# homeboard18.net
KiCad netlist of a schematic drawn in EAGLE
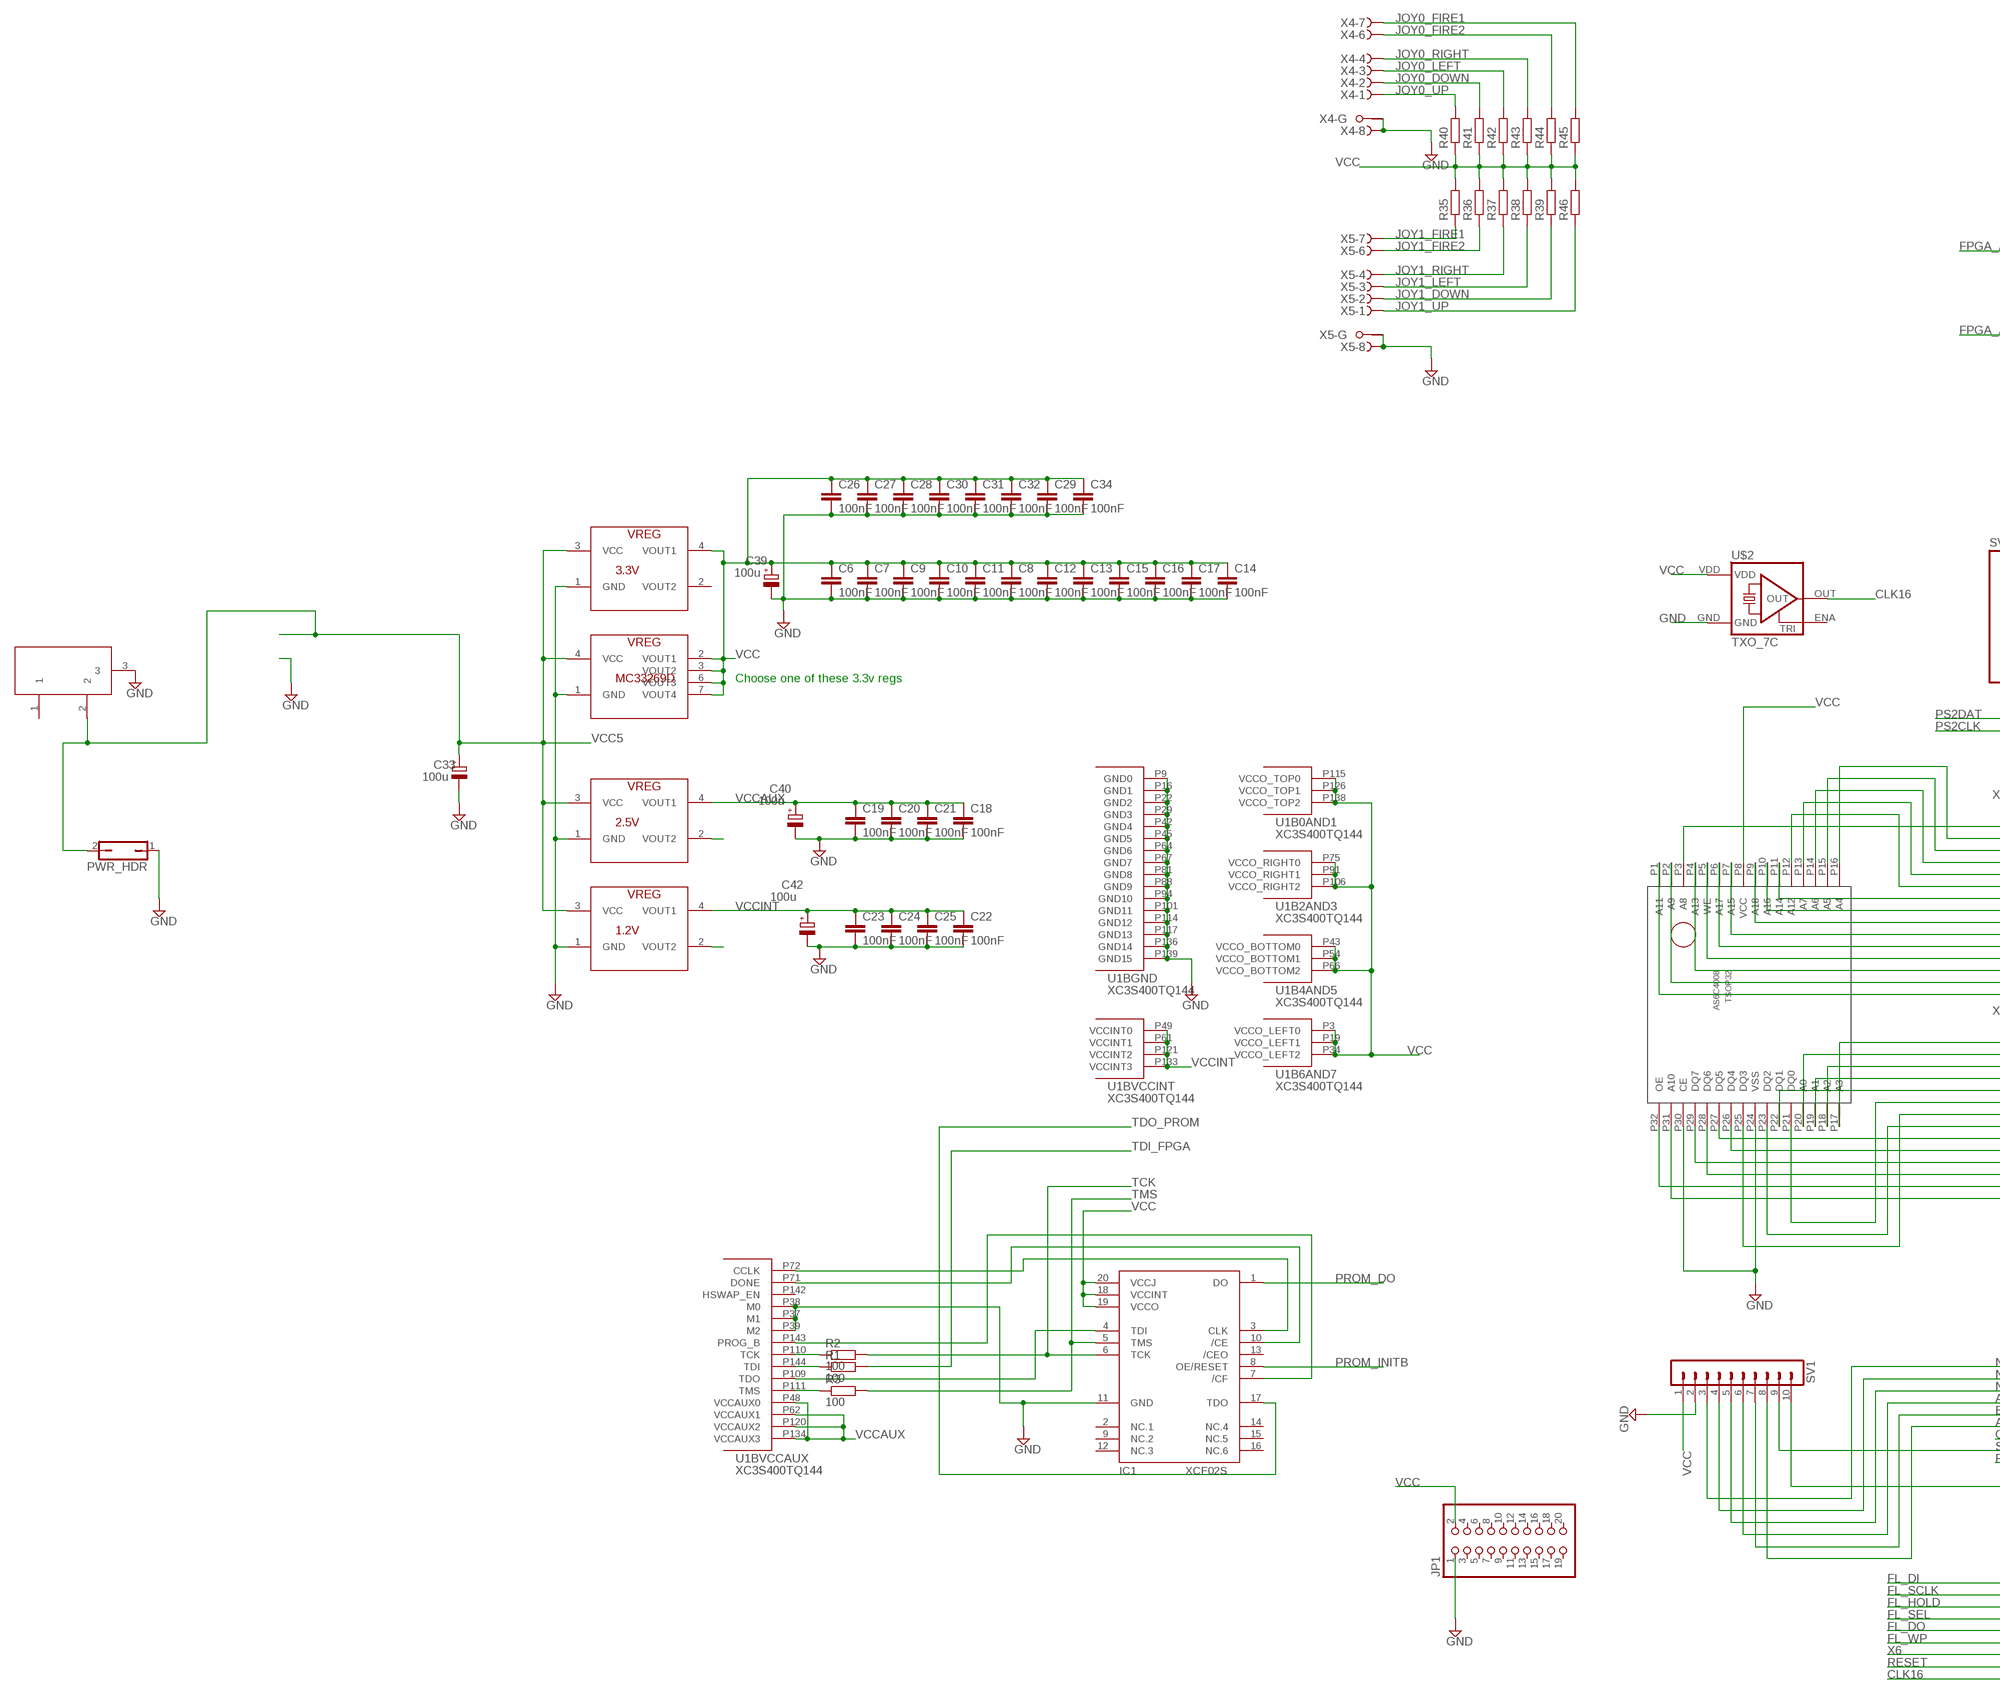
[diagram p0: schematic, sheet 1, part 1 of 3]
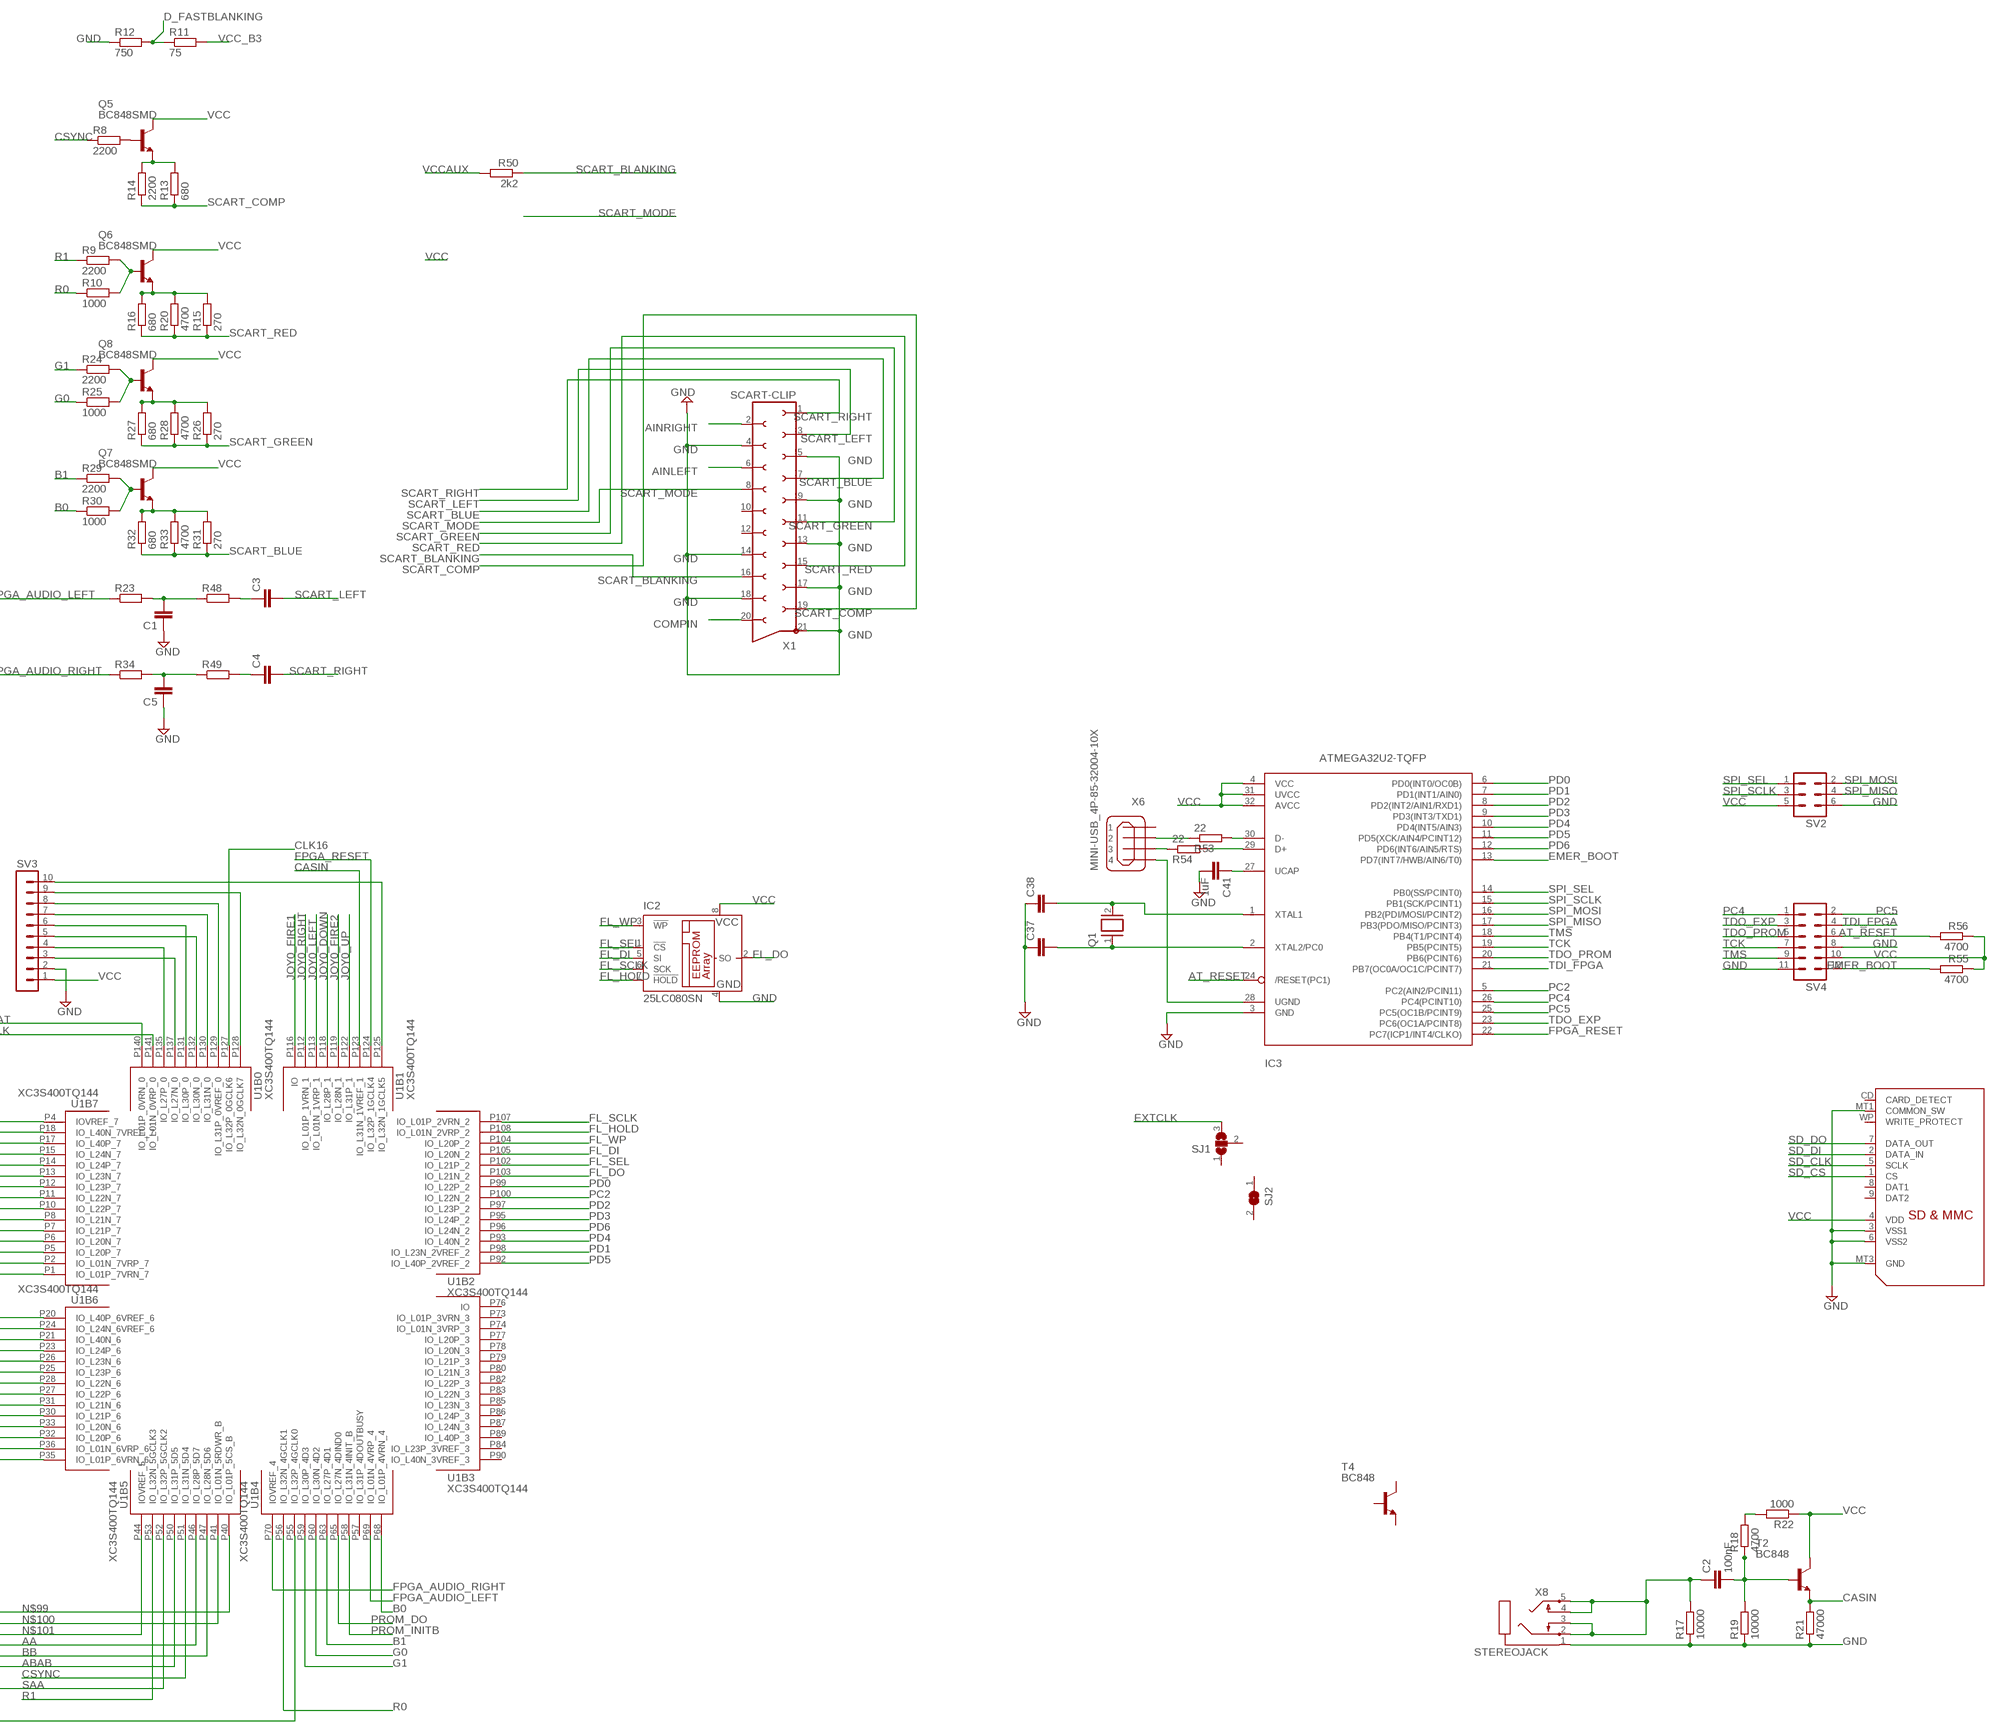
[diagram p1: schematic, sheet 1, part 2 of 3]
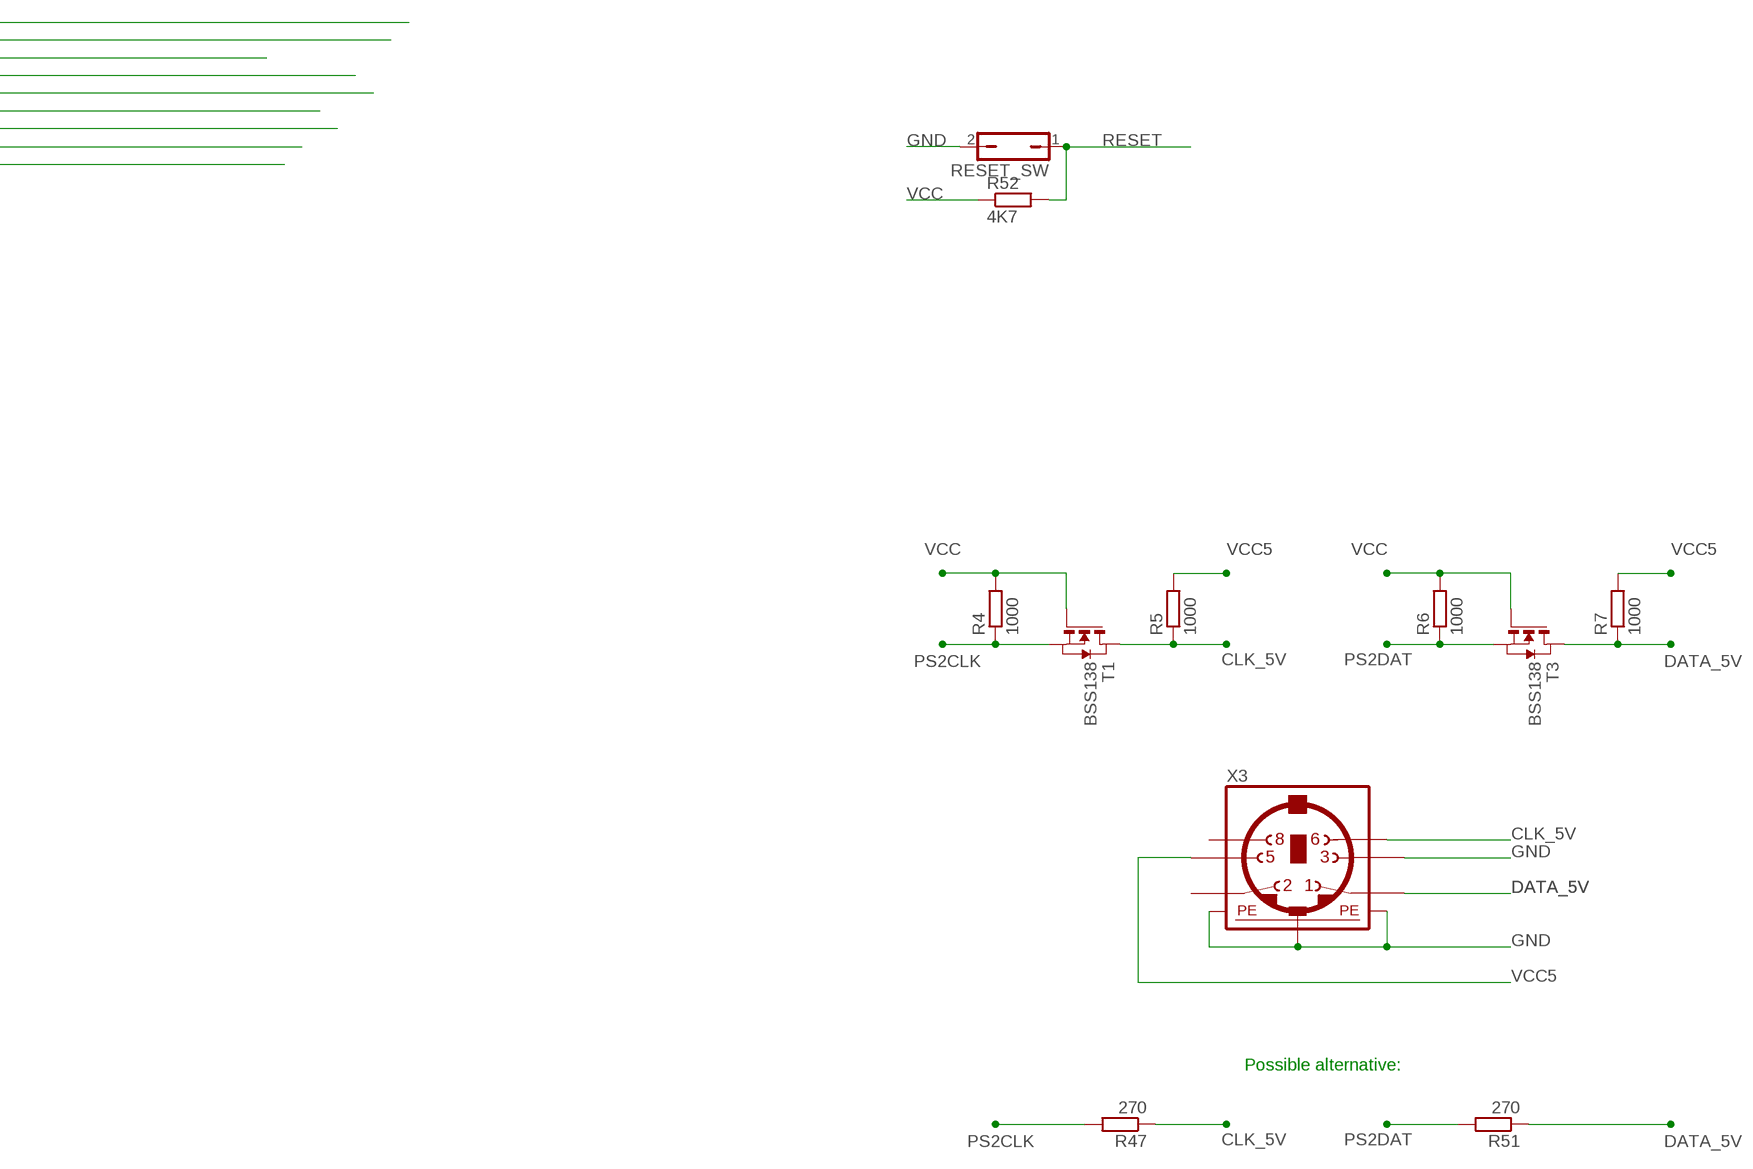
[diagram p2: schematic, sheet 1, part 3 of 3]

(export (version "E")
  (design (tool "Eeschema 10.0.6"))
  (components
    (comp (ref "C1")
      (value "C-EUC0603")
      (footprint "eagle-import:C0603")
      (libsource (lib "eagle-import") (part "resistor_C-EUC0603"))
    )
    (comp (ref "C2")
      (value "100nF")
      (footprint "eagle-import:C0603")
      (libsource (lib "eagle-import") (part "resistor_C-EUC0603"))
    )
    (comp (ref "C3")
      (value "C-EUC0603")
      (footprint "eagle-import:C0603")
      (libsource (lib "eagle-import") (part "resistor_C-EUC0603"))
    )
    (comp (ref "C4")
      (value "C-EUC0603")
      (footprint "eagle-import:C0603")
      (libsource (lib "eagle-import") (part "resistor_C-EUC0603"))
    )
    (comp (ref "C5")
      (value "C-EUC0603")
      (footprint "eagle-import:C0603")
      (libsource (lib "eagle-import") (part "resistor_C-EUC0603"))
    )
    (comp (ref "C6")
      (value "100nF")
      (footprint "eagle-import:C0603")
      (libsource (lib "eagle-import") (part "C-EUC0603"))
    )
    (comp (ref "C7")
      (value "100nF")
      (footprint "eagle-import:C0603")
      (libsource (lib "eagle-import") (part "C-EUC0603"))
    )
    (comp (ref "C8")
      (value "100nF")
      (footprint "eagle-import:C0603")
      (libsource (lib "eagle-import") (part "C-EUC0603"))
    )
    (comp (ref "C9")
      (value "100nF")
      (footprint "eagle-import:C0603")
      (libsource (lib "eagle-import") (part "C-EUC0603"))
    )
    (comp (ref "C10")
      (value "100nF")
      (footprint "eagle-import:C0603")
      (libsource (lib "eagle-import") (part "C-EUC0603"))
    )
    (comp (ref "C11")
      (value "100nF")
      (footprint "eagle-import:C0603")
      (libsource (lib "eagle-import") (part "C-EUC0603"))
    )
    (comp (ref "C12")
      (value "100nF")
      (footprint "eagle-import:C0603")
      (libsource (lib "eagle-import") (part "C-EUC0603"))
    )
    (comp (ref "C13")
      (value "100nF")
      (footprint "eagle-import:C0603")
      (libsource (lib "eagle-import") (part "C-EUC0603"))
    )
    (comp (ref "C14")
      (value "100nF")
      (footprint "eagle-import:C0603")
      (libsource (lib "eagle-import") (part "C-EUC0603"))
    )
    (comp (ref "C15")
      (value "100nF")
      (footprint "eagle-import:C0603")
      (libsource (lib "eagle-import") (part "C-EUC0603"))
    )
    (comp (ref "C16")
      (value "100nF")
      (footprint "eagle-import:C0603")
      (libsource (lib "eagle-import") (part "C-EUC0603"))
    )
    (comp (ref "C17")
      (value "100nF")
      (footprint "eagle-import:C0603")
      (libsource (lib "eagle-import") (part "C-EUC0603"))
    )
    (comp (ref "C18")
      (value "100nF")
      (footprint "eagle-import:C0603")
      (libsource (lib "eagle-import") (part "C-EUC0603"))
    )
    (comp (ref "C19")
      (value "100nF")
      (footprint "eagle-import:C0603")
      (libsource (lib "eagle-import") (part "C-EUC0603"))
    )
    (comp (ref "C20")
      (value "100nF")
      (footprint "eagle-import:C0603")
      (libsource (lib "eagle-import") (part "C-EUC0603"))
    )
    (comp (ref "C21")
      (value "100nF")
      (footprint "eagle-import:C0603")
      (libsource (lib "eagle-import") (part "C-EUC0603"))
    )
    (comp (ref "C22")
      (value "100nF")
      (footprint "eagle-import:C0603")
      (libsource (lib "eagle-import") (part "C-EUC0603"))
    )
    (comp (ref "C23")
      (value "100nF")
      (footprint "eagle-import:C0603")
      (libsource (lib "eagle-import") (part "C-EUC0603"))
    )
    (comp (ref "C24")
      (value "100nF")
      (footprint "eagle-import:C0603")
      (libsource (lib "eagle-import") (part "C-EUC0603"))
    )
    (comp (ref "C25")
      (value "100nF")
      (footprint "eagle-import:C0603")
      (libsource (lib "eagle-import") (part "C-EUC0603"))
    )
    (comp (ref "C26")
      (value "100nF")
      (footprint "eagle-import:C0603")
      (libsource (lib "eagle-import") (part "C-EUC0603"))
    )
    (comp (ref "C27")
      (value "100nF")
      (footprint "eagle-import:C0603")
      (libsource (lib "eagle-import") (part "C-EUC0603"))
    )
    (comp (ref "C28")
      (value "100nF")
      (footprint "eagle-import:C0603")
      (libsource (lib "eagle-import") (part "C-EUC0603"))
    )
    (comp (ref "C29")
      (value "100nF")
      (footprint "eagle-import:C0603")
      (libsource (lib "eagle-import") (part "C-EUC0603"))
    )
    (comp (ref "C30")
      (value "100nF")
      (footprint "eagle-import:C0603")
      (libsource (lib "eagle-import") (part "C-EUC0603"))
    )
    (comp (ref "C31")
      (value "100nF")
      (footprint "eagle-import:C0603")
      (libsource (lib "eagle-import") (part "C-EUC0603"))
    )
    (comp (ref "C32")
      (value "100nF")
      (footprint "eagle-import:C0603")
      (libsource (lib "eagle-import") (part "C-EUC0603"))
    )
    (comp (ref "C33")
      (value "100u")
      (footprint "eagle-import:PANASONIC_D")
      (libsource (lib "eagle-import") (part "CPOL-EUD"))
    )
    (comp (ref "C34")
      (value "100nF")
      (footprint "eagle-import:C0603")
      (libsource (lib "eagle-import") (part "C-EUC0603"))
    )
    (comp (ref "C37")
      (value "C-EUC0805")
      (footprint "eagle-import:C0805")
      (libsource (lib "eagle-import") (part "C-EUC0805"))
    )
    (comp (ref "C38")
      (value "C-EUC0805")
      (footprint "eagle-import:C0805")
      (libsource (lib "eagle-import") (part "C-EUC0805"))
    )
    (comp (ref "C39")
      (value "100u")
      (footprint "eagle-import:PANASONIC_D")
      (libsource (lib "eagle-import") (part "CPOL-EUD"))
    )
    (comp (ref "C40")
      (value "100u")
      (footprint "eagle-import:PANASONIC_D")
      (libsource (lib "eagle-import") (part "CPOL-EUD"))
    )
    (comp (ref "C41")
      (value "1uF")
      (footprint "eagle-import:C0805")
      (libsource (lib "eagle-import") (part "C-EUC0805"))
    )
    (comp (ref "C42")
      (value "100u")
      (footprint "eagle-import:PANASONIC_D")
      (libsource (lib "eagle-import") (part "CPOL-EUD"))
    )
    (comp (ref "IC1")
      (value "XCF02S")
      (footprint "eagle-import:VO20")
      (libsource (lib "eagle-import") (part "XCF02S"))
    )
    (comp (ref "IC2")
      (value "25LC080SN")
      (footprint "eagle-import:SO-08")
      (fields (field (name "MF") "MICROCHIP") (field (name "MPN") "25LC080/SN"))
      (libsource (lib "eagle-import") (part "25SNLC080"))
    )
    (comp (ref "IC3")
      (value "ATMEGA32U2-TQFP")
      (footprint "eagle-import:TQFP32-08")
      (libsource (lib "eagle-import") (part "ATMEGA32U2-TQFP"))
    )
    (comp (ref "JP1")
      (value "PINHD-2X10")
      (footprint "eagle-import:2X10")
      (libsource (lib "eagle-import") (part "PINHD-2X10"))
    )
    (comp (ref "PWR_HDR")
      (value "JP1Q")
      (footprint "eagle-import:JP1")
      (libsource (lib "eagle-import") (part "JP1Q"))
    )
    (comp (ref "Q1")
      (value "XTAL/S")
      (footprint "eagle-import:QS")
      (libsource (lib "eagle-import") (part "XTAL/S"))
    )
    (comp (ref "Q5")
      (value "BC848SMD")
      (footprint "eagle-import:SOT23")
      (libsource (lib "eagle-import") (part "BC848SMD"))
    )
    (comp (ref "Q6")
      (value "BC848SMD")
      (footprint "eagle-import:SOT23")
      (libsource (lib "eagle-import") (part "BC848SMD"))
    )
    (comp (ref "Q7")
      (value "BC848SMD")
      (footprint "eagle-import:SOT23")
      (libsource (lib "eagle-import") (part "BC848SMD"))
    )
    (comp (ref "Q8")
      (value "BC848SMD")
      (footprint "eagle-import:SOT23")
      (libsource (lib "eagle-import") (part "BC848SMD"))
    )
    (comp (ref "R1")
      (value "100")
      (footprint "eagle-import:R0805")
      (libsource (lib "eagle-import") (part "R-EU_R0805"))
    )
    (comp (ref "R2")
      (value "100")
      (footprint "eagle-import:R0805")
      (libsource (lib "eagle-import") (part "R-EU_R0805"))
    )
    (comp (ref "R3")
      (value "100")
      (footprint "eagle-import:R0805")
      (libsource (lib "eagle-import") (part "R-EU_R0805"))
    )
    (comp (ref "R4")
      (value "1000")
      (footprint "eagle-import:R0805")
      (libsource (lib "eagle-import") (part "R-EU_R0805"))
    )
    (comp (ref "R5")
      (value "1000")
      (footprint "eagle-import:R0805")
      (libsource (lib "eagle-import") (part "R-EU_R0805"))
    )
    (comp (ref "R6")
      (value "1000")
      (footprint "eagle-import:R0805")
      (libsource (lib "eagle-import") (part "R-EU_R0805"))
    )
    (comp (ref "R7")
      (value "1000")
      (footprint "eagle-import:R0805")
      (libsource (lib "eagle-import") (part "R-EU_R0805"))
    )
    (comp (ref "R8")
      (value "2200")
      (footprint "eagle-import:R0805")
      (libsource (lib "eagle-import") (part "R-EU_R0805"))
    )
    (comp (ref "R9")
      (value "2200")
      (footprint "eagle-import:R0805")
      (libsource (lib "eagle-import") (part "R-EU_R0805"))
    )
    (comp (ref "R10")
      (value "1000")
      (footprint "eagle-import:R0805")
      (libsource (lib "eagle-import") (part "R-EU_R0805"))
    )
    (comp (ref "R11")
      (value "75")
      (footprint "eagle-import:R0805")
      (libsource (lib "eagle-import") (part "R-EU_R0805"))
    )
    (comp (ref "R12")
      (value "750")
      (footprint "eagle-import:R0805")
      (libsource (lib "eagle-import") (part "R-EU_R0805"))
    )
    (comp (ref "R13")
      (value "680")
      (footprint "eagle-import:R0805")
      (libsource (lib "eagle-import") (part "R-EU_R0805"))
    )
    (comp (ref "R14")
      (value "2200")
      (footprint "eagle-import:R0805")
      (libsource (lib "eagle-import") (part "R-EU_R0805"))
    )
    (comp (ref "R15")
      (value "270")
      (footprint "eagle-import:R0805")
      (libsource (lib "eagle-import") (part "R-EU_R0805"))
    )
    (comp (ref "R16")
      (value "680")
      (footprint "eagle-import:R0805")
      (libsource (lib "eagle-import") (part "R-EU_R0805"))
    )
    (comp (ref "R17")
      (value "10000")
      (footprint "eagle-import:R0805")
      (libsource (lib "eagle-import") (part "R-EU_R0805"))
    )
    (comp (ref "R18")
      (value "4700")
      (footprint "eagle-import:R0805")
      (libsource (lib "eagle-import") (part "R-EU_R0805"))
    )
    (comp (ref "R19")
      (value "10000")
      (footprint "eagle-import:R0805")
      (libsource (lib "eagle-import") (part "R-EU_R0805"))
    )
    (comp (ref "R20")
      (value "4700")
      (footprint "eagle-import:R0805")
      (libsource (lib "eagle-import") (part "R-EU_R0805"))
    )
    (comp (ref "R21")
      (value "47000")
      (footprint "eagle-import:R0805")
      (libsource (lib "eagle-import") (part "R-EU_R0805"))
    )
    (comp (ref "R22")
      (value "1000")
      (footprint "eagle-import:R0805")
      (libsource (lib "eagle-import") (part "R-EU_R0805"))
    )
    (comp (ref "R23")
      (value "R-EU_M0805")
      (footprint "eagle-import:M0805")
      (libsource (lib "eagle-import") (part "resistor_R-EU_M0805"))
    )
    (comp (ref "R24")
      (value "2200")
      (footprint "eagle-import:R0805")
      (libsource (lib "eagle-import") (part "R-EU_R0805"))
    )
    (comp (ref "R25")
      (value "1000")
      (footprint "eagle-import:R0805")
      (libsource (lib "eagle-import") (part "R-EU_R0805"))
    )
    (comp (ref "R26")
      (value "270")
      (footprint "eagle-import:R0805")
      (libsource (lib "eagle-import") (part "R-EU_R0805"))
    )
    (comp (ref "R27")
      (value "680")
      (footprint "eagle-import:R0805")
      (libsource (lib "eagle-import") (part "R-EU_R0805"))
    )
    (comp (ref "R28")
      (value "4700")
      (footprint "eagle-import:R0805")
      (libsource (lib "eagle-import") (part "R-EU_R0805"))
    )
    (comp (ref "R29")
      (value "2200")
      (footprint "eagle-import:R0805")
      (libsource (lib "eagle-import") (part "R-EU_R0805"))
    )
    (comp (ref "R30")
      (value "1000")
      (footprint "eagle-import:R0805")
      (libsource (lib "eagle-import") (part "R-EU_R0805"))
    )
    (comp (ref "R31")
      (value "270")
      (footprint "eagle-import:R0805")
      (libsource (lib "eagle-import") (part "R-EU_R0805"))
    )
    (comp (ref "R32")
      (value "680")
      (footprint "eagle-import:R0805")
      (libsource (lib "eagle-import") (part "R-EU_R0805"))
    )
    (comp (ref "R33")
      (value "4700")
      (footprint "eagle-import:R0805")
      (libsource (lib "eagle-import") (part "R-EU_R0805"))
    )
    (comp (ref "R34")
      (value "R-EU_M0805")
      (footprint "eagle-import:M0805")
      (libsource (lib "eagle-import") (part "resistor_R-EU_M0805"))
    )
    (comp (ref "R35")
      (value "R-EU_M0805")
      (footprint "eagle-import:M0805")
      (libsource (lib "eagle-import") (part "resistor_R-EU_M0805"))
    )
    (comp (ref "R36")
      (value "R-EU_M0805")
      (footprint "eagle-import:M0805")
      (libsource (lib "eagle-import") (part "resistor_R-EU_M0805"))
    )
    (comp (ref "R37")
      (value "R-EU_M0805")
      (footprint "eagle-import:M0805")
      (libsource (lib "eagle-import") (part "resistor_R-EU_M0805"))
    )
    (comp (ref "R38")
      (value "R-EU_M0805")
      (footprint "eagle-import:M0805")
      (libsource (lib "eagle-import") (part "resistor_R-EU_M0805"))
    )
    (comp (ref "R39")
      (value "R-EU_M0805")
      (footprint "eagle-import:M0805")
      (libsource (lib "eagle-import") (part "resistor_R-EU_M0805"))
    )
    (comp (ref "R40")
      (value "R-EU_M0805")
      (footprint "eagle-import:M0805")
      (libsource (lib "eagle-import") (part "resistor_R-EU_M0805"))
    )
    (comp (ref "R41")
      (value "R-EU_M0805")
      (footprint "eagle-import:M0805")
      (libsource (lib "eagle-import") (part "resistor_R-EU_M0805"))
    )
    (comp (ref "R42")
      (value "R-EU_M0805")
      (footprint "eagle-import:M0805")
      (libsource (lib "eagle-import") (part "resistor_R-EU_M0805"))
    )
    (comp (ref "R43")
      (value "R-EU_M0805")
      (footprint "eagle-import:M0805")
      (libsource (lib "eagle-import") (part "resistor_R-EU_M0805"))
    )
    (comp (ref "R44")
      (value "R-EU_M0805")
      (footprint "eagle-import:M0805")
      (libsource (lib "eagle-import") (part "resistor_R-EU_M0805"))
    )
    (comp (ref "R45")
      (value "R-EU_M0805")
      (footprint "eagle-import:M0805")
      (libsource (lib "eagle-import") (part "resistor_R-EU_M0805"))
    )
    (comp (ref "R46")
      (value "R-EU_M0805")
      (footprint "eagle-import:M0805")
      (libsource (lib "eagle-import") (part "resistor_R-EU_M0805"))
    )
    (comp (ref "R47")
      (value "270")
      (footprint "eagle-import:R0805")
      (libsource (lib "eagle-import") (part "R-EU_R0805"))
    )
    (comp (ref "R48")
      (value "R-EU_M0805")
      (footprint "eagle-import:M0805")
      (libsource (lib "eagle-import") (part "resistor_R-EU_M0805"))
    )
    (comp (ref "R49")
      (value "R-EU_M0805")
      (footprint "eagle-import:M0805")
      (libsource (lib "eagle-import") (part "resistor_R-EU_M0805"))
    )
    (comp (ref "R50")
      (value "2k2")
      (footprint "eagle-import:M0805")
      (libsource (lib "eagle-import") (part "resistor_R-EU_M0805"))
    )
    (comp (ref "R51")
      (value "270")
      (footprint "eagle-import:R0805")
      (libsource (lib "eagle-import") (part "R-EU_R0805"))
    )
    (comp (ref "R52")
      (value "4K7")
      (footprint "eagle-import:M0805")
      (libsource (lib "eagle-import") (part "resistor_R-EU_M0805"))
    )
    (comp (ref "R53")
      (value "22")
      (footprint "eagle-import:R0805")
      (libsource (lib "eagle-import") (part "R-EU_R0805"))
    )
    (comp (ref "R54")
      (value "22")
      (footprint "eagle-import:R0805")
      (libsource (lib "eagle-import") (part "R-EU_R0805"))
    )
    (comp (ref "R55")
      (value "4700")
      (footprint "eagle-import:R0805")
      (libsource (lib "eagle-import") (part "R-EU_R0805"))
    )
    (comp (ref "R56")
      (value "4700")
      (footprint "eagle-import:R0805")
      (libsource (lib "eagle-import") (part "R-EU_R0805"))
    )
    (comp (ref "REG1.2")
      (value "1.2V")
      (footprint "eagle-import:SOT223")
      (libsource (lib "eagle-import") (part "NX1117"))
    )
    (comp (ref "REG2.5")
      (value "2.5V")
      (footprint "eagle-import:SOT223")
      (libsource (lib "eagle-import") (part "NX1117"))
    )
    (comp (ref "RESET_SW")
      (value "JP1Q")
      (footprint "eagle-import:JP1")
      (libsource (lib "eagle-import") (part "JP1Q"))
    )
    (comp (ref "SJ1")
      (value "SJ2W")
      (footprint "eagle-import:SJ_2")
      (libsource (lib "eagle-import") (part "SJ2W"))
    )
    (comp (ref "SJ2") (value "SJ") (footprint "eagle-import:SJ") (libsource (lib "eagle-import") (part "SJ")))
    (comp (ref "SV1")
      (value "MA10-1")
      (footprint "eagle-import:MA10-1")
      (fields (field (name "OC_FARNELL") "unknown") (field (name "OC_NEWARK") "unknown"))
      (libsource (lib "eagle-import") (part "MA10-1"))
    )
    (comp (ref "SV2")
      (value "MA03-2")
      (footprint "eagle-import:MA03-2")
      (libsource (lib "eagle-import") (part "MA03-2"))
    )
    (comp (ref "SV3")
      (value "MA10-1")
      (footprint "eagle-import:MA10-1")
      (libsource (lib "eagle-import") (part "MA10-1"))
    )
    (comp (ref "SV4")
      (value "MA06-2")
      (footprint "eagle-import:MA06-2")
      (libsource (lib "eagle-import") (part "MA06-2"))
    )
    (comp (ref "T1")
      (value "BSS138")
      (footprint "eagle-import:SOT-23")
      (libsource (lib "eagle-import") (part "NMOSSOT23"))
    )
    (comp (ref "T2")
      (value "BC848")
      (footprint "eagle-import:SOT23")
      (libsource (lib "eagle-import") (part "BC848"))
    )
    (comp (ref "T3")
      (value "BSS138")
      (footprint "eagle-import:SOT-23")
      (libsource (lib "eagle-import") (part "NMOSSOT23"))
    )
    (comp (ref "T4")
      (value "BC848")
      (footprint "eagle-import:SOT23")
      (libsource (lib "eagle-import") (part "BC848"))
    )
    (comp (ref "U$2")
      (value "TXO_7C")
      (footprint "eagle-import:OSC_7C")
      (libsource (lib "eagle-import") (part "TXO_7C"))
    )
    (comp (ref "U$3")
      (value "SDMMCNOHOLE")
      (footprint "eagle-import:SDCARD-NOHOLE")
      (libsource (lib "eagle-import") (part "SDMMCNOHOLE"))
    )
    (comp (ref "U$4")
      (value "3.3V")
      (footprint "eagle-import:SOT223")
      (libsource (lib "eagle-import") (part "NX1117"))
    )
    (comp (ref "U$5")
      (value "MC33269D")
      (footprint "eagle-import:SO8")
      (libsource (lib "eagle-import") (part "MC33269D"))
    )
    (comp (ref "U$6")
      (value "AS6C4008")
      (footprint "eagle-import:TSOP32")
      (libsource (lib "eagle-import") (part "AS6C4008"))
    )
    (comp (ref "U1")
      (value "XC3S400TQ144")
      (footprint "eagle-import:TQ144")
      (libsource (lib "eagle-import") (part "XC3S400TQ144"))
    )
    (comp (ref "X1")
      (value "SCART-CLIP")
      (footprint "eagle-import:SCART-CLIP")
      (libsource (lib "eagle-import") (part "SCART-CLIP"))
    )
    (comp (ref "X3")
      (value "MINI_DIN_6")
      (footprint "eagle-import:M_DIN6")
      (libsource (lib "eagle-import") (part "MINI_DIN_6"))
    )
    (comp (ref "X4")
      (value "F09HPS")
      (footprint "eagle-import:F09HP")
      (libsource (lib "eagle-import") (part "F09HPS"))
    )
    (comp (ref "X5")
      (value "F09HPS")
      (footprint "eagle-import:F09HP")
      (libsource (lib "eagle-import") (part "F09HPS"))
    )
    (comp (ref "X6")
      (value "MINI-USB_4P-85-32004-10X")
      (footprint "eagle-import:85-32004-10X")
      (libsource (lib "eagle-import") (part "MINI-USB_4P-85-32004-10X"))
    )
    (comp (ref "X7")
      (value "DC21MMX")
      (footprint "eagle-import:DC-21MM")
      (libsource (lib "eagle-import") (part "DC21MMX"))
    )
    (comp (ref "X8")
      (value "STEREOJACK")
      (footprint "eagle-import:20-0137")
      (libsource (lib "eagle-import") (part "STEREOJACK"))
    )
  )
  (nets
    (net (code "1") (name "/1") (class "Default")
      (node (ref "X7") (pin "1") (pinfunction "1_1") (pintype "power_in"))
    )
    (net (code "2") (name "/AA") (class "Default")
      (node (ref "SV1") (pin "6") (pinfunction "6_6") (pintype "passive"))
      (node (ref "U1") (pin "P46") (pinfunction "IO_L28P_5D7_P46") (pintype "bidirectional"))
    )
    (net (code "3") (name "/ABAB") (class "Default")
      (node (ref "SV1") (pin "8") (pinfunction "8_8") (pintype "passive"))
      (node (ref "U1") (pin "P50") (pinfunction "IO_L31P_5D5_P50") (pintype "bidirectional"))
    )
    (net (code "4") (name "/AINLEFT") (class "Default")
      (node (ref "X1") (pin "6") (pinfunction "6_6") (pintype "passive"))
    )
    (net (code "5") (name "/AINRIGHT") (class "Default")
      (node (ref "X1") (pin "2") (pinfunction "2_2") (pintype "passive"))
    )
    (net (code "6") (name "/AT_RESET") (class "Default")
      (node (ref "IC3") (pin "24") (pinfunction "/RESET(PC1)_24") (pintype "bidirectional"))
      (node (ref "R56") (pin "2") (pinfunction "2_2") (pintype "passive"))
      (node (ref "SV4") (pin "6") (pinfunction "6_6") (pintype "passive"))
    )
    (net (code "7") (name "/B0") (class "Default")
      (node (ref "R30") (pin "1") (pinfunction "1_1") (pintype "passive"))
      (node (ref "U1") (pin "P68") (pinfunction "IO_L01P_4VRN_4_P68") (pintype "bidirectional"))
    )
    (net (code "8") (name "/B1") (class "Default")
      (node (ref "R29") (pin "1") (pinfunction "1_1") (pintype "passive"))
      (node (ref "U1") (pin "P63") (pinfunction "IO_L27P_4D1_P63") (pintype "bidirectional"))
    )
    (net (code "9") (name "/BB") (class "Default")
      (node (ref "SV1") (pin "7") (pinfunction "7_7") (pintype "passive"))
      (node (ref "U1") (pin "P47") (pinfunction "IO_L28N_5D6_P47") (pintype "bidirectional"))
    )
    (net (code "10") (name "/CASIN") (class "Default")
      (node (ref "R21") (pin "2") (pinfunction "2_2") (pintype "passive"))
      (node (ref "T2") (pin "2") (pinfunction "E_2") (pintype "passive"))
      (node (ref "U1") (pin "P123") (pinfunction "IO_L31N_1VREF_1_P123") (pintype "bidirectional"))
    )
    (net (code "11") (name "/CLK16") (class "Default")
      (node (ref "U$2") (pin "OUT") (pinfunction "OUT_OUT") (pintype "output"))
      (node (ref "U1") (pin "P127") (pinfunction "IO_L32P_0GCLK6_P127") (pintype "bidirectional"))
    )
    (net (code "12") (name "/CLK_5V") (class "Default")
      (node (ref "R47") (pin "1") (pinfunction "1_1") (pintype "passive"))
      (node (ref "R5") (pin "1") (pinfunction "1_1") (pintype "passive"))
      (node (ref "T1") (pin "1") (pinfunction "D_1") (pintype "passive"))
      (node (ref "X3") (pin "6") (pinfunction "6_6") (pintype "passive"))
    )
    (net (code "13") (name "/COMPIN") (class "Default")
      (node (ref "X1") (pin "20") (pinfunction "20_20") (pintype "passive"))
    )
    (net (code "14") (name "/CSYNC") (class "Default")
      (node (ref "R8") (pin "1") (pinfunction "1_1") (pintype "passive"))
      (node (ref "U1") (pin "P51") (pinfunction "IO_L31N_5D4_P51") (pintype "bidirectional"))
    )
    (net (code "15") (name "/DATA_5V") (class "Default")
      (node (ref "R51") (pin "1") (pinfunction "1_1") (pintype "passive"))
      (node (ref "R7") (pin "1") (pinfunction "1_1") (pintype "passive"))
      (node (ref "T3") (pin "1") (pinfunction "D_1") (pintype "passive"))
      (node (ref "X3") (pin "1") (pinfunction "1_1") (pintype "passive"))
    )
    (net (code "16") (name "/D_FASTBLANKING") (class "Default")
      (node (ref "R11") (pin "1") (pinfunction "1_1") (pintype "passive"))
      (node (ref "R12") (pin "2") (pinfunction "2_2") (pintype "passive"))
    )
    (net (code "17") (name "/EMER_BOOT") (class "Default")
      (node (ref "IC3") (pin "13") (pinfunction "PD7(INT7/HWB/AIN6/T0)_13") (pintype "bidirectional"))
      (node (ref "R55") (pin "2") (pinfunction "2_2") (pintype "passive"))
      (node (ref "SV4") (pin "12") (pinfunction "12_12") (pintype "passive"))
    )
    (net (code "18") (name "/EXTCLK") (class "Default")
      (node (ref "SJ1") (pin "3") (pinfunction "3_3") (pintype "passive"))
    )
    (net (code "19") (name "/FL_DI") (class "Default")
      (node (ref "IC2") (pin "5") (pinfunction "SI_5") (pintype "input"))
      (node (ref "U1") (pin "P105") (pinfunction "IO_L20N_2_P105") (pintype "bidirectional"))
    )
    (net (code "20") (name "/FL_DO") (class "Default")
      (node (ref "IC2") (pin "2") (pinfunction "SO_2") (pintype "bidirectional"))
      (node (ref "U1") (pin "P103") (pinfunction "IO_L21N_2_P103") (pintype "bidirectional"))
    )
    (net (code "21") (name "/FL_HOLD") (class "Default")
      (node (ref "IC2") (pin "7") (pinfunction "~{HOLD}_7") (pintype "input"))
      (node (ref "U1") (pin "P108") (pinfunction "IO_L01N_2VRP_2_P108") (pintype "bidirectional"))
    )
    (net (code "22") (name "/FL_SCLK") (class "Default")
      (node (ref "IC2") (pin "6") (pinfunction "SCK_6") (pintype "input"))
      (node (ref "U1") (pin "P107") (pinfunction "IO_L01P_2VRN_2_P107") (pintype "bidirectional"))
    )
    (net (code "23") (name "/FL_SEL") (class "Default")
      (node (ref "IC2") (pin "1") (pinfunction "~{CS}_1") (pintype "input"))
      (node (ref "U1") (pin "P102") (pinfunction "IO_L21P_2_P102") (pintype "bidirectional"))
    )
    (net (code "24") (name "/FL_WP") (class "Default")
      (node (ref "IC2") (pin "3") (pinfunction "~{WP}_3") (pintype "input"))
      (node (ref "U1") (pin "P104") (pinfunction "IO_L20P_2_P104") (pintype "bidirectional"))
    )
    (net (code "25") (name "/FPGA_AUDIO_LEFT") (class "Default")
      (node (ref "R23") (pin "1") (pinfunction "1_1") (pintype "passive"))
      (node (ref "U1") (pin "P69") (pinfunction "IO_L01N_4VRP_4_P69") (pintype "bidirectional"))
    )
    (net (code "26") (name "/FPGA_AUDIO_RIGHT") (class "Default")
      (node (ref "R34") (pin "1") (pinfunction "1_1") (pintype "passive"))
      (node (ref "U1") (pin "P70") (pinfunction "IOVREF_4_P70") (pintype "bidirectional"))
    )
    (net (code "27") (name "/FPGA_RESET") (class "Default")
      (node (ref "IC3") (pin "22") (pinfunction "PC7(ICP1/INT4/CLKO)_22") (pintype "bidirectional"))
      (node (ref "U1") (pin "P124") (pinfunction "IO_L32P_1GCLK4_P124") (pintype "bidirectional"))
    )
    (net (code "28") (name "/G0") (class "Default")
      (node (ref "R25") (pin "1") (pinfunction "1_1") (pintype "passive"))
      (node (ref "U1") (pin "P60") (pinfunction "IO_L30N_4D2_P60") (pintype "bidirectional"))
    )
    (net (code "29") (name "/G1") (class "Default")
      (node (ref "R24") (pin "1") (pinfunction "1_1") (pintype "passive"))
      (node (ref "U1") (pin "P59") (pinfunction "IO_L30P_4D3_P59") (pintype "bidirectional"))
    )
    (net (code "30") (name "/JOY0_DOWN") (class "Default")
      (node (ref "R41") (pin "2") (pinfunction "2_2") (pintype "passive"))
      (node (ref "U1") (pin "P118") (pinfunction "IO_L28P_1_P118") (pintype "bidirectional"))
      (node (ref "X4") (pin "2") (pinfunction "F_2") (pintype "passive"))
    )
    (net (code "31") (name "/JOY0_FIRE1") (class "Default")
      (node (ref "R45") (pin "2") (pinfunction "2_2") (pintype "passive"))
      (node (ref "U1") (pin "P116") (pinfunction "IO_P116") (pintype "bidirectional"))
      (node (ref "X4") (pin "7") (pinfunction "F_7") (pintype "passive"))
    )
    (net (code "32") (name "/JOY0_FIRE2") (class "Default")
      (node (ref "R44") (pin "2") (pinfunction "2_2") (pintype "passive"))
      (node (ref "U1") (pin "P119") (pinfunction "IO_L28N_1_P119") (pintype "bidirectional"))
      (node (ref "X4") (pin "6") (pinfunction "F_6") (pintype "passive"))
    )
    (net (code "33") (name "/JOY0_LEFT") (class "Default")
      (node (ref "R42") (pin "2") (pinfunction "2_2") (pintype "passive"))
      (node (ref "U1") (pin "P113") (pinfunction "IO_L01N_1VRP_1_P113") (pintype "bidirectional"))
      (node (ref "X4") (pin "3") (pinfunction "F_3") (pintype "passive"))
    )
    (net (code "34") (name "/JOY0_RIGHT") (class "Default")
      (node (ref "R43") (pin "2") (pinfunction "2_2") (pintype "passive"))
      (node (ref "U1") (pin "P112") (pinfunction "IO_L01P_1VRN_1_P112") (pintype "bidirectional"))
      (node (ref "X4") (pin "4") (pinfunction "F_4") (pintype "passive"))
    )
    (net (code "35") (name "/JOY0_UP") (class "Default")
      (node (ref "R40") (pin "2") (pinfunction "2_2") (pintype "passive"))
      (node (ref "U1") (pin "P122") (pinfunction "IO_L31P_1_P122") (pintype "bidirectional"))
      (node (ref "X4") (pin "1") (pinfunction "F_1") (pintype "passive"))
    )
    (net (code "36") (name "/JOY1_DOWN") (class "Default")
      (node (ref "R39") (pin "1") (pinfunction "1_1") (pintype "passive"))
      (node (ref "X5") (pin "2") (pinfunction "F_2") (pintype "passive"))
    )
    (net (code "37") (name "/JOY1_FIRE1") (class "Default")
      (node (ref "R35") (pin "1") (pinfunction "1_1") (pintype "passive"))
      (node (ref "X5") (pin "7") (pinfunction "F_7") (pintype "passive"))
    )
    (net (code "38") (name "/JOY1_FIRE2") (class "Default")
      (node (ref "R36") (pin "1") (pinfunction "1_1") (pintype "passive"))
      (node (ref "X5") (pin "6") (pinfunction "F_6") (pintype "passive"))
    )
    (net (code "39") (name "/JOY1_LEFT") (class "Default")
      (node (ref "R38") (pin "1") (pinfunction "1_1") (pintype "passive"))
      (node (ref "X5") (pin "3") (pinfunction "F_3") (pintype "passive"))
    )
    (net (code "40") (name "/JOY1_RIGHT") (class "Default")
      (node (ref "R37") (pin "1") (pinfunction "1_1") (pintype "passive"))
      (node (ref "X5") (pin "4") (pinfunction "F_4") (pintype "passive"))
    )
    (net (code "41") (name "/JOY1_UP") (class "Default")
      (node (ref "R46") (pin "1") (pinfunction "1_1") (pintype "passive"))
      (node (ref "X5") (pin "1") (pinfunction "F_1") (pintype "passive"))
    )
    (net (code "42") (name "/N$99") (class "Default")
      (node (ref "SV1") (pin "3") (pinfunction "3_3") (pintype "passive"))
      (node (ref "U1") (pin "P40") (pinfunction "IO_L01P_5CS_B_P40") (pintype "bidirectional"))
    )
    (net (code "43") (name "/N$100") (class "Default")
      (node (ref "SV1") (pin "4") (pinfunction "4_4") (pintype "passive"))
      (node (ref "U1") (pin "P41") (pinfunction "IO_L01N_5RDWR_B_P41") (pintype "bidirectional"))
    )
    (net (code "44") (name "/N$101") (class "Default")
      (node (ref "SV1") (pin "5") (pinfunction "5_5") (pintype "passive"))
      (node (ref "U1") (pin "P44") (pinfunction "IOVREF_5_P44") (pintype "bidirectional"))
    )
    (net (code "45") (name "/PC2") (class "Default")
      (node (ref "IC3") (pin "5") (pinfunction "PC2(AIN2/PCIN11)_5") (pintype "bidirectional"))
      (node (ref "U1") (pin "P100") (pinfunction "IO_L22N_2_P100") (pintype "bidirectional"))
    )
    (net (code "46") (name "/PC4") (class "Default")
      (node (ref "IC3") (pin "26") (pinfunction "PC4(PCINT10)_26") (pintype "bidirectional"))
      (node (ref "SV4") (pin "1") (pinfunction "1_1") (pintype "passive"))
    )
    (net (code "47") (name "/PC5") (class "Default")
      (node (ref "IC3") (pin "25") (pinfunction "PC5(OC1B/PCINT9)_25") (pintype "bidirectional"))
      (node (ref "SV4") (pin "2") (pinfunction "2_2") (pintype "passive"))
    )
    (net (code "48") (name "/PD0") (class "Default")
      (node (ref "IC3") (pin "6") (pinfunction "PD0(INT0/OC0B)_6") (pintype "bidirectional"))
      (node (ref "U1") (pin "P99") (pinfunction "IO_L22P_2_P99") (pintype "bidirectional"))
    )
    (net (code "49") (name "/PD1") (class "Default")
      (node (ref "IC3") (pin "7") (pinfunction "PD1(INT1/AIN0)_7") (pintype "bidirectional"))
      (node (ref "U1") (pin "P98") (pinfunction "IO_L23N_2VREF_2_P98") (pintype "bidirectional"))
    )
    (net (code "50") (name "/PD2") (class "Default")
      (node (ref "IC3") (pin "8") (pinfunction "PD2(INT2/AIN1/RXD1)_8") (pintype "bidirectional"))
      (node (ref "U1") (pin "P97") (pinfunction "IO_L23P_2_P97") (pintype "bidirectional"))
    )
    (net (code "51") (name "/PD3") (class "Default")
      (node (ref "IC3") (pin "9") (pinfunction "PD3(INT3/TXD1)_9") (pintype "bidirectional"))
      (node (ref "U1") (pin "P95") (pinfunction "IO_L24P_2_P95") (pintype "bidirectional"))
    )
    (net (code "52") (name "/PD4") (class "Default")
      (node (ref "IC3") (pin "10") (pinfunction "PD4(INT5/AIN3)_10") (pintype "bidirectional"))
      (node (ref "U1") (pin "P93") (pinfunction "IO_L40N_2_P93") (pintype "bidirectional"))
    )
    (net (code "53") (name "/PD5") (class "Default")
      (node (ref "IC3") (pin "11") (pinfunction "PD5(XCK/AIN4/PCINT12)_11") (pintype "bidirectional"))
      (node (ref "U1") (pin "P92") (pinfunction "IO_L40P_2VREF_2_P92") (pintype "bidirectional"))
    )
    (net (code "54") (name "/PD6") (class "Default")
      (node (ref "IC3") (pin "12") (pinfunction "PD6(INT6/AIN5/RTS)_12") (pintype "bidirectional"))
      (node (ref "U1") (pin "P96") (pinfunction "IO_L24N_2_P96") (pintype "bidirectional"))
    )
    (net (code "55") (name "/PROM_DO") (class "Default")
      (node (ref "IC1") (pin "1") (pinfunction "DO_1") (pintype "bidirectional"))
      (node (ref "U1") (pin "P65") (pinfunction "IO_L27N_4DIND0_P65") (pintype "bidirectional"))
    )
    (net (code "56") (name "/PROM_INITB") (class "Default")
      (node (ref "IC1") (pin "8") (pinfunction "OE/RESET_8") (pintype "bidirectional"))
      (node (ref "U1") (pin "P58") (pinfunction "IO_L31N_4INIT_B_P58") (pintype "bidirectional"))
    )
    (net (code "57") (name "/PS2CLK") (class "Default")
      (node (ref "R4") (pin "1") (pinfunction "1_1") (pintype "passive"))
      (node (ref "R47") (pin "2") (pinfunction "2_2") (pintype "passive"))
      (node (ref "T1") (pin "2") (pinfunction "S_2") (pintype "passive"))
      (node (ref "U1") (pin "P141") (pinfunction "IO_L01N_0VRP_0_P141") (pintype "bidirectional"))
    )
    (net (code "58") (name "/PS2DAT") (class "Default")
      (node (ref "R51") (pin "2") (pinfunction "2_2") (pintype "passive"))
      (node (ref "R6") (pin "1") (pinfunction "1_1") (pintype "passive"))
      (node (ref "T3") (pin "2") (pinfunction "S_2") (pintype "passive"))
      (node (ref "U1") (pin "P140") (pinfunction "IO_L01P_0VRN_0_P140") (pintype "bidirectional"))
    )
    (net (code "59") (name "/R0") (class "Default")
      (node (ref "R10") (pin "1") (pinfunction "1_1") (pintype "passive"))
      (node (ref "U1") (pin "P56") (pinfunction "IO_L32N_4GCLK1_P56") (pintype "bidirectional"))
    )
    (net (code "60") (name "/R1") (class "Default")
      (node (ref "R9") (pin "1") (pinfunction "1_1") (pintype "passive"))
      (node (ref "U1") (pin "P53") (pinfunction "IO_L32N_5GCLK3_P53") (pintype "bidirectional"))
    )
    (net (code "61") (name "/RESET") (class "Default")
      (node (ref "R52") (pin "2") (pinfunction "2_2") (pintype "passive"))
      (node (ref "RESET_SW") (pin "1") (pinfunction "1_1") (pintype "passive"))
    )
    (net (code "62") (name "/SAA") (class "Default")
      (node (ref "SV1") (pin "9") (pinfunction "9_9") (pintype "passive"))
      (node (ref "U1") (pin "P52") (pinfunction "IO_L32P_5GCLK2_P52") (pintype "bidirectional"))
    )
    (net (code "63") (name "/SCART_BLANKING") (class "Default")
      (node (ref "R50") (pin "1") (pinfunction "1_1") (pintype "passive"))
      (node (ref "X1") (pin "16") (pinfunction "16_16") (pintype "passive"))
    )
    (net (code "64") (name "/SCART_BLUE") (class "Default")
      (node (ref "R31") (pin "1") (pinfunction "1_1") (pintype "passive"))
      (node (ref "R32") (pin "1") (pinfunction "1_1") (pintype "passive"))
      (node (ref "R33") (pin "1") (pinfunction "1_1") (pintype "passive"))
      (node (ref "X1") (pin "7") (pinfunction "7_7") (pintype "passive"))
    )
    (net (code "65") (name "/SCART_COMP") (class "Default")
      (node (ref "R13") (pin "1") (pinfunction "1_1") (pintype "passive"))
      (node (ref "R14") (pin "1") (pinfunction "1_1") (pintype "passive"))
      (node (ref "X1") (pin "19") (pinfunction "19_19") (pintype "passive"))
    )
    (net (code "66") (name "/SCART_GREEN") (class "Default")
      (node (ref "R26") (pin "1") (pinfunction "1_1") (pintype "passive"))
      (node (ref "R27") (pin "1") (pinfunction "1_1") (pintype "passive"))
      (node (ref "R28") (pin "1") (pinfunction "1_1") (pintype "passive"))
      (node (ref "X1") (pin "11") (pinfunction "11_11") (pintype "passive"))
    )
    (net (code "67") (name "/SCART_LEFT") (class "Default")
      (node (ref "C3") (pin "2") (pinfunction "2_2") (pintype "passive"))
      (node (ref "X1") (pin "3") (pinfunction "3_3") (pintype "passive"))
    )
    (net (code "68") (name "/SCART_MODE") (class "Default")
      (node (ref "X1") (pin "8") (pinfunction "8_8") (pintype "passive"))
    )
    (net (code "69") (name "/SCART_RED") (class "Default")
      (node (ref "R15") (pin "1") (pinfunction "1_1") (pintype "passive"))
      (node (ref "R16") (pin "1") (pinfunction "1_1") (pintype "passive"))
      (node (ref "R20") (pin "1") (pinfunction "1_1") (pintype "passive"))
      (node (ref "X1") (pin "15") (pinfunction "15_15") (pintype "passive"))
    )
    (net (code "70") (name "/SCART_RIGHT") (class "Default")
      (node (ref "C4") (pin "2") (pinfunction "2_2") (pintype "passive"))
      (node (ref "X1") (pin "1") (pinfunction "1_1") (pintype "passive"))
    )
    (net (code "71") (name "/SD_CLK") (class "Default")
      (node (ref "U$3") (pin "5") (pinfunction "SCLK_5") (pintype "input"))
    )
    (net (code "72") (name "/SD_CS") (class "Default")
      (node (ref "U$3") (pin "1") (pinfunction "CS_1") (pintype "input"))
    )
    (net (code "73") (name "/SD_DI") (class "Default")
      (node (ref "U$3") (pin "2") (pinfunction "DATA_IN_2") (pintype "input"))
    )
    (net (code "74") (name "/SD_DO") (class "Default")
      (node (ref "U$3") (pin "7") (pinfunction "DATA_OUT_7") (pintype "output"))
    )
    (net (code "75") (name "/SPI_MISO") (class "Default")
      (node (ref "IC3") (pin "17") (pinfunction "PB3(PDO/MISO/PCINT3)_17") (pintype "bidirectional"))
      (node (ref "SV2") (pin "4") (pinfunction "4_4") (pintype "passive"))
    )
    (net (code "76") (name "/SPI_MOSI") (class "Default")
      (node (ref "IC3") (pin "16") (pinfunction "PB2(PDI/MOSI/PCINT2)_16") (pintype "bidirectional"))
      (node (ref "SV2") (pin "2") (pinfunction "2_2") (pintype "passive"))
    )
    (net (code "77") (name "/SPI_SCLK") (class "Default")
      (node (ref "IC3") (pin "15") (pinfunction "PB1(SCK/PCINT1)_15") (pintype "bidirectional"))
      (node (ref "SV2") (pin "3") (pinfunction "3_3") (pintype "passive"))
    )
    (net (code "78") (name "/SPI_SEL") (class "Default")
      (node (ref "IC3") (pin "14") (pinfunction "PB0(SS/PCINT0)_14") (pintype "bidirectional"))
      (node (ref "SV2") (pin "1") (pinfunction "1_1") (pintype "passive"))
    )
    (net (code "79") (name "/TCK") (class "Default")
      (node (ref "IC1") (pin "6") (pinfunction "TCK_6") (pintype "bidirectional"))
      (node (ref "IC3") (pin "19") (pinfunction "PB5(PCINT5)_19") (pintype "bidirectional"))
      (node (ref "R2") (pin "2") (pinfunction "2_2") (pintype "passive"))
      (node (ref "SV4") (pin "7") (pinfunction "7_7") (pintype "passive"))
    )
    (net (code "80") (name "/TDI_FPGA") (class "Default")
      (node (ref "IC3") (pin "21") (pinfunction "PB7(OC0A/OC1C/PCINT7)_21") (pintype "bidirectional"))
      (node (ref "R1") (pin "2") (pinfunction "2_2") (pintype "passive"))
      (node (ref "SV4") (pin "4") (pinfunction "4_4") (pintype "passive"))
    )
    (net (code "81") (name "/TDO_EXP") (class "Default")
      (node (ref "IC3") (pin "23") (pinfunction "PC6(OC1A/PCINT8)_23") (pintype "bidirectional"))
      (node (ref "SV4") (pin "3") (pinfunction "3_3") (pintype "passive"))
    )
    (net (code "82") (name "/TDO_PROM") (class "Default")
      (node (ref "IC1") (pin "17") (pinfunction "TDO_17") (pintype "bidirectional"))
      (node (ref "IC3") (pin "20") (pinfunction "PB6(PCINT6)_20") (pintype "bidirectional"))
      (node (ref "SV4") (pin "5") (pinfunction "5_5") (pintype "passive"))
    )
    (net (code "83") (name "/TMS") (class "Default")
      (node (ref "IC1") (pin "5") (pinfunction "TMS_5") (pintype "bidirectional"))
      (node (ref "IC3") (pin "18") (pinfunction "PB4(T1/PCINT4)_18") (pintype "bidirectional"))
      (node (ref "R3") (pin "2") (pinfunction "2_2") (pintype "passive"))
      (node (ref "SV4") (pin "9") (pinfunction "9_9") (pintype "passive"))
    )
    (net (code "84") (name "/VCC") (class "Default")
      (node (ref "C10") (pin "1") (pinfunction "1_1") (pintype "passive"))
      (node (ref "C11") (pin "1") (pinfunction "1_1") (pintype "passive"))
      (node (ref "C12") (pin "1") (pinfunction "1_1") (pintype "passive"))
      (node (ref "C13") (pin "1") (pinfunction "1_1") (pintype "passive"))
      (node (ref "C14") (pin "1") (pinfunction "1_1") (pintype "passive"))
      (node (ref "C15") (pin "1") (pinfunction "1_1") (pintype "passive"))
      (node (ref "C16") (pin "1") (pinfunction "1_1") (pintype "passive"))
      (node (ref "C17") (pin "1") (pinfunction "1_1") (pintype "passive"))
      (node (ref "C26") (pin "1") (pinfunction "1_1") (pintype "passive"))
      (node (ref "C27") (pin "1") (pinfunction "1_1") (pintype "passive"))
      (node (ref "C28") (pin "1") (pinfunction "1_1") (pintype "passive"))
      (node (ref "C29") (pin "1") (pinfunction "1_1") (pintype "passive"))
      (node (ref "C30") (pin "1") (pinfunction "1_1") (pintype "passive"))
      (node (ref "C31") (pin "1") (pinfunction "1_1") (pintype "passive"))
      (node (ref "C32") (pin "1") (pinfunction "1_1") (pintype "passive"))
      (node (ref "C34") (pin "1") (pinfunction "1_1") (pintype "passive"))
      (node (ref "C39") (pin "+") (pinfunction "+_+") (pintype "passive"))
      (node (ref "C6") (pin "1") (pinfunction "1_1") (pintype "passive"))
      (node (ref "C7") (pin "1") (pinfunction "1_1") (pintype "passive"))
      (node (ref "C8") (pin "1") (pinfunction "1_1") (pintype "passive"))
      (node (ref "C9") (pin "1") (pinfunction "1_1") (pintype "passive"))
      (node (ref "IC1") (pin "18") (pinfunction "VCCINT_18") (pintype "bidirectional"))
      (node (ref "IC1") (pin "19") (pinfunction "VCCO_19") (pintype "bidirectional"))
      (node (ref "IC1") (pin "20") (pinfunction "VCCJ_20") (pintype "bidirectional"))
      (node (ref "IC2") (pin "8") (pinfunction "VCC_8") (pintype "power_in"))
      (node (ref "IC3") (pin "31") (pinfunction "UVCC_31") (pintype "bidirectional"))
      (node (ref "IC3") (pin "32") (pinfunction "AVCC_32") (pintype "bidirectional"))
      (node (ref "IC3") (pin "4") (pinfunction "VCC_4") (pintype "bidirectional"))
      (node (ref "JP1") (pin "2") (pinfunction "2_2") (pintype "passive"))
      (node (ref "Q5") (pin "3") (pinfunction "C_3") (pintype "passive"))
      (node (ref "Q6") (pin "3") (pinfunction "C_3") (pintype "passive"))
      (node (ref "Q7") (pin "3") (pinfunction "C_3") (pintype "passive"))
      (node (ref "Q8") (pin "3") (pinfunction "C_3") (pintype "passive"))
      (node (ref "R22") (pin "1") (pinfunction "1_1") (pintype "passive"))
      (node (ref "R35") (pin "2") (pinfunction "2_2") (pintype "passive"))
      (node (ref "R36") (pin "2") (pinfunction "2_2") (pintype "passive"))
      (node (ref "R37") (pin "2") (pinfunction "2_2") (pintype "passive"))
      (node (ref "R38") (pin "2") (pinfunction "2_2") (pintype "passive"))
      (node (ref "R39") (pin "2") (pinfunction "2_2") (pintype "passive"))
      (node (ref "R4") (pin "2") (pinfunction "2_2") (pintype "passive"))
      (node (ref "R40") (pin "1") (pinfunction "1_1") (pintype "passive"))
      (node (ref "R41") (pin "1") (pinfunction "1_1") (pintype "passive"))
      (node (ref "R42") (pin "1") (pinfunction "1_1") (pintype "passive"))
      (node (ref "R43") (pin "1") (pinfunction "1_1") (pintype "passive"))
      (node (ref "R44") (pin "1") (pinfunction "1_1") (pintype "passive"))
      (node (ref "R45") (pin "1") (pinfunction "1_1") (pintype "passive"))
      (node (ref "R46") (pin "2") (pinfunction "2_2") (pintype "passive"))
      (node (ref "R52") (pin "1") (pinfunction "1_1") (pintype "passive"))
      (node (ref "R55") (pin "1") (pinfunction "1_1") (pintype "passive"))
      (node (ref "R56") (pin "1") (pinfunction "1_1") (pintype "passive"))
      (node (ref "R6") (pin "2") (pinfunction "2_2") (pintype "passive"))
      (node (ref "SV1") (pin "1") (pinfunction "1_1") (pintype "passive"))
      (node (ref "SV2") (pin "5") (pinfunction "5_5") (pintype "passive"))
      (node (ref "SV3") (pin "1") (pinfunction "1_1") (pintype "passive"))
      (node (ref "SV4") (pin "10") (pinfunction "10_10") (pintype "passive"))
      (node (ref "T1") (pin "3") (pinfunction "G_3") (pintype "passive"))
      (node (ref "T2") (pin "3") (pinfunction "C_3") (pintype "passive"))
      (node (ref "T3") (pin "3") (pinfunction "G_3") (pintype "passive"))
      (node (ref "U$2") (pin "VDD") (pinfunction "VDD_VDD") (pintype "power_in"))
      (node (ref "U$3") (pin "4") (pinfunction "VDD_4") (pintype "power_in"))
      (node (ref "U$4") (pin "4") (pinfunction "VOUT1_4") (pintype "bidirectional"))
      (node (ref "U$5") (pin "2") (pinfunction "VOUT1_2") (pintype "output"))
      (node (ref "U$5") (pin "3") (pinfunction "VOUT2_3") (pintype "output"))
      (node (ref "U$5") (pin "6") (pinfunction "VOUT3_6") (pintype "output"))
      (node (ref "U$5") (pin "7") (pinfunction "VOUT4_7") (pintype "output"))
      (node (ref "U$6") (pin "P8") (pinfunction "VCC_P8") (pintype "bidirectional"))
      (node (ref "U1") (pin "P106") (pinfunction "VCCO_RIGHT2_P106") (pintype "passive"))
      (node (ref "U1") (pin "P115") (pinfunction "VCCO_TOP0_P115") (pintype "passive"))
      (node (ref "U1") (pin "P126") (pinfunction "VCCO_TOP1_P126") (pintype "passive"))
      (node (ref "U1") (pin "P138") (pinfunction "VCCO_TOP2_P138") (pintype "passive"))
      (node (ref "U1") (pin "P19") (pinfunction "VCCO_LEFT1_P19") (pintype "passive"))
      (node (ref "U1") (pin "P3") (pinfunction "VCCO_LEFT0_P3") (pintype "passive"))
      (node (ref "U1") (pin "P34") (pinfunction "VCCO_LEFT2_P34") (pintype "passive"))
      (node (ref "U1") (pin "P43") (pinfunction "VCCO_BOTTOM0_P43") (pintype "passive"))
      (node (ref "U1") (pin "P54") (pinfunction "VCCO_BOTTOM1_P54") (pintype "passive"))
      (node (ref "U1") (pin "P66") (pinfunction "VCCO_BOTTOM2_P66") (pintype "passive"))
      (node (ref "U1") (pin "P75") (pinfunction "VCCO_RIGHT0_P75") (pintype "passive"))
      (node (ref "U1") (pin "P91") (pinfunction "VCCO_RIGHT1_P91") (pintype "passive"))
    )
    (net (code "85") (name "/VCC5") (class "Default")
      (node (ref "C33") (pin "+") (pinfunction "+_+") (pintype "passive"))
      (node (ref "PWR_HDR") (pin "2") (pinfunction "2_2") (pintype "passive"))
      (node (ref "R5") (pin "2") (pinfunction "2_2") (pintype "passive"))
      (node (ref "R7") (pin "2") (pinfunction "2_2") (pintype "passive"))
      (node (ref "REG1.2") (pin "3") (pinfunction "VCC_3") (pintype "bidirectional"))
      (node (ref "REG2.5") (pin "3") (pinfunction "VCC_3") (pintype "bidirectional"))
      (node (ref "U$4") (pin "3") (pinfunction "VCC_3") (pintype "bidirectional"))
      (node (ref "U$5") (pin "4") (pinfunction "VCC_4") (pintype "bidirectional"))
      (node (ref "X3") (pin "5") (pinfunction "5_5") (pintype "passive"))
      (node (ref "X7") (pin "2") (pinfunction "2_2") (pintype "power_in"))
    )
    (net (code "86") (name "/VCCAUX") (class "Default")
      (node (ref "C18") (pin "1") (pinfunction "1_1") (pintype "passive"))
      (node (ref "C19") (pin "1") (pinfunction "1_1") (pintype "passive"))
      (node (ref "C20") (pin "1") (pinfunction "1_1") (pintype "passive"))
      (node (ref "C21") (pin "1") (pinfunction "1_1") (pintype "passive"))
      (node (ref "C40") (pin "+") (pinfunction "+_+") (pintype "passive"))
      (node (ref "R50") (pin "2") (pinfunction "2_2") (pintype "passive"))
      (node (ref "REG2.5") (pin "4") (pinfunction "VOUT1_4") (pintype "bidirectional"))
      (node (ref "U1") (pin "P120") (pinfunction "VCCAUX2_P120") (pintype "passive"))
      (node (ref "U1") (pin "P134") (pinfunction "VCCAUX3_P134") (pintype "passive"))
      (node (ref "U1") (pin "P48") (pinfunction "VCCAUX0_P48") (pintype "passive"))
      (node (ref "U1") (pin "P62") (pinfunction "VCCAUX1_P62") (pintype "passive"))
    )
    (net (code "87") (name "/VCCINT") (class "Default")
      (node (ref "C22") (pin "1") (pinfunction "1_1") (pintype "passive"))
      (node (ref "C23") (pin "1") (pinfunction "1_1") (pintype "passive"))
      (node (ref "C24") (pin "1") (pinfunction "1_1") (pintype "passive"))
      (node (ref "C25") (pin "1") (pinfunction "1_1") (pintype "passive"))
      (node (ref "C42") (pin "+") (pinfunction "+_+") (pintype "passive"))
      (node (ref "REG1.2") (pin "4") (pinfunction "VOUT1_4") (pintype "bidirectional"))
      (node (ref "U1") (pin "P121") (pinfunction "VCCINT2_P121") (pintype "passive"))
      (node (ref "U1") (pin "P133") (pinfunction "VCCINT3_P133") (pintype "passive"))
      (node (ref "U1") (pin "P49") (pinfunction "VCCINT0_P49") (pintype "passive"))
      (node (ref "U1") (pin "P61") (pinfunction "VCCINT1_P61") (pintype "passive"))
    )
    (net (code "88") (name "/VCC_B3") (class "Default")
      (node (ref "R11") (pin "2") (pinfunction "2_2") (pintype "passive"))
    )
    (net (code "90") (name "GND") (class "Default")
      (node (ref "C1") (pin "1") (pinfunction "1_1") (pintype "passive"))
      (node (ref "C10") (pin "2") (pinfunction "2_2") (pintype "passive"))
      (node (ref "C11") (pin "2") (pinfunction "2_2") (pintype "passive"))
      (node (ref "C12") (pin "2") (pinfunction "2_2") (pintype "passive"))
      (node (ref "C13") (pin "2") (pinfunction "2_2") (pintype "passive"))
      (node (ref "C14") (pin "2") (pinfunction "2_2") (pintype "passive"))
      (node (ref "C15") (pin "2") (pinfunction "2_2") (pintype "passive"))
      (node (ref "C16") (pin "2") (pinfunction "2_2") (pintype "passive"))
      (node (ref "C17") (pin "2") (pinfunction "2_2") (pintype "passive"))
      (node (ref "C18") (pin "2") (pinfunction "2_2") (pintype "passive"))
      (node (ref "C19") (pin "2") (pinfunction "2_2") (pintype "passive"))
      (node (ref "C20") (pin "2") (pinfunction "2_2") (pintype "passive"))
      (node (ref "C21") (pin "2") (pinfunction "2_2") (pintype "passive"))
      (node (ref "C22") (pin "2") (pinfunction "2_2") (pintype "passive"))
      (node (ref "C23") (pin "2") (pinfunction "2_2") (pintype "passive"))
      (node (ref "C24") (pin "2") (pinfunction "2_2") (pintype "passive"))
      (node (ref "C25") (pin "2") (pinfunction "2_2") (pintype "passive"))
      (node (ref "C26") (pin "2") (pinfunction "2_2") (pintype "passive"))
      (node (ref "C27") (pin "2") (pinfunction "2_2") (pintype "passive"))
      (node (ref "C28") (pin "2") (pinfunction "2_2") (pintype "passive"))
      (node (ref "C29") (pin "2") (pinfunction "2_2") (pintype "passive"))
      (node (ref "C30") (pin "2") (pinfunction "2_2") (pintype "passive"))
      (node (ref "C31") (pin "2") (pinfunction "2_2") (pintype "passive"))
      (node (ref "C32") (pin "2") (pinfunction "2_2") (pintype "passive"))
      (node (ref "C33") (pin "-") (pinfunction "-_-") (pintype "passive"))
      (node (ref "C34") (pin "2") (pinfunction "2_2") (pintype "passive"))
      (node (ref "C37") (pin "1") (pinfunction "1_1") (pintype "passive"))
      (node (ref "C38") (pin "1") (pinfunction "1_1") (pintype "passive"))
      (node (ref "C39") (pin "-") (pinfunction "-_-") (pintype "passive"))
      (node (ref "C40") (pin "-") (pinfunction "-_-") (pintype "passive"))
      (node (ref "C41") (pin "2") (pinfunction "2_2") (pintype "passive"))
      (node (ref "C42") (pin "-") (pinfunction "-_-") (pintype "passive"))
      (node (ref "C5") (pin "1") (pinfunction "1_1") (pintype "passive"))
      (node (ref "C6") (pin "2") (pinfunction "2_2") (pintype "passive"))
      (node (ref "C7") (pin "2") (pinfunction "2_2") (pintype "passive"))
      (node (ref "C8") (pin "2") (pinfunction "2_2") (pintype "passive"))
      (node (ref "C9") (pin "2") (pinfunction "2_2") (pintype "passive"))
      (node (ref "IC1") (pin "11") (pinfunction "GND_11") (pintype "bidirectional"))
      (node (ref "IC2") (pin "4") (pinfunction "GND_4") (pintype "power_in"))
      (node (ref "IC3") (pin "3") (pinfunction "GND_3") (pintype "bidirectional"))
      (node (ref "JP1") (pin "1") (pinfunction "1_1") (pintype "passive"))
      (node (ref "PWR_HDR") (pin "1") (pinfunction "1_1") (pintype "passive"))
      (node (ref "R12") (pin "1") (pinfunction "1_1") (pintype "passive"))
      (node (ref "R17") (pin "1") (pinfunction "1_1") (pintype "passive"))
      (node (ref "R19") (pin "1") (pinfunction "1_1") (pintype "passive"))
      (node (ref "R21") (pin "1") (pinfunction "1_1") (pintype "passive"))
      (node (ref "REG1.2") (pin "1") (pinfunction "GND_1") (pintype "bidirectional"))
      (node (ref "REG2.5") (pin "1") (pinfunction "GND_1") (pintype "bidirectional"))
      (node (ref "RESET_SW") (pin "2") (pinfunction "2_2") (pintype "passive"))
      (node (ref "SV1") (pin "2") (pinfunction "2_2") (pintype "passive"))
      (node (ref "SV2") (pin "6") (pinfunction "6_6") (pintype "passive"))
      (node (ref "SV3") (pin "2") (pinfunction "2_2") (pintype "passive"))
      (node (ref "SV4") (pin "11") (pinfunction "11_11") (pintype "passive"))
      (node (ref "SV4") (pin "8") (pinfunction "8_8") (pintype "passive"))
      (node (ref "U$2") (pin "GND") (pinfunction "GND_GND") (pintype "power_in"))
      (node (ref "U$3") (pin "3") (pinfunction "VSS1_3") (pintype "power_in"))
      (node (ref "U$3") (pin "6") (pinfunction "VSS2_6") (pintype "power_in"))
      (node (ref "U$3") (pin "MT1") (pinfunction "COMMON_SW_MT1") (pintype "passive"))
      (node (ref "U$3") (pin "MT3") (pinfunction "GND_MT3") (pintype "power_in"))
      (node (ref "U$4") (pin "1") (pinfunction "GND_1") (pintype "bidirectional"))
      (node (ref "U$5") (pin "1") (pinfunction "GND_1") (pintype "bidirectional"))
      (node (ref "U$6") (pin "P24") (pinfunction "VSS_P24") (pintype "bidirectional"))
      (node (ref "U$6") (pin "P30") (pinfunction "CE_P30") (pintype "bidirectional"))
      (node (ref "U1") (pin "P101") (pinfunction "GND11_P101") (pintype "passive"))
      (node (ref "U1") (pin "P114") (pinfunction "GND12_P114") (pintype "passive"))
      (node (ref "U1") (pin "P117") (pinfunction "GND13_P117") (pintype "passive"))
      (node (ref "U1") (pin "P136") (pinfunction "GND14_P136") (pintype "passive"))
      (node (ref "U1") (pin "P139") (pinfunction "GND15_P139") (pintype "passive"))
      (node (ref "U1") (pin "P16") (pinfunction "GND1_P16") (pintype "passive"))
      (node (ref "U1") (pin "P22") (pinfunction "GND2_P22") (pintype "passive"))
      (node (ref "U1") (pin "P29") (pinfunction "GND3_P29") (pintype "passive"))
      (node (ref "U1") (pin "P37") (pinfunction "M1_P37") (pintype "bidirectional"))
      (node (ref "U1") (pin "P38") (pinfunction "M0_P38") (pintype "bidirectional"))
      (node (ref "U1") (pin "P39") (pinfunction "M2_P39") (pintype "bidirectional"))
      (node (ref "U1") (pin "P42") (pinfunction "GND4_P42") (pintype "passive"))
      (node (ref "U1") (pin "P45") (pinfunction "GND5_P45") (pintype "passive"))
      (node (ref "U1") (pin "P64") (pinfunction "GND6_P64") (pintype "passive"))
      (node (ref "U1") (pin "P67") (pinfunction "GND7_P67") (pintype "passive"))
      (node (ref "U1") (pin "P81") (pinfunction "GND8_P81") (pintype "passive"))
      (node (ref "U1") (pin "P88") (pinfunction "GND9_P88") (pintype "passive"))
      (node (ref "U1") (pin "P9") (pinfunction "GND0_P9") (pintype "passive"))
      (node (ref "U1") (pin "P94") (pinfunction "GND10_P94") (pintype "passive"))
      (node (ref "X1") (pin "13") (pinfunction "13_13") (pintype "passive"))
      (node (ref "X1") (pin "14") (pinfunction "14_14") (pintype "passive"))
      (node (ref "X1") (pin "17") (pinfunction "17_17") (pintype "passive"))
      (node (ref "X1") (pin "18") (pinfunction "18_18") (pintype "passive"))
      (node (ref "X1") (pin "21") (pinfunction "21_21") (pintype "passive"))
      (node (ref "X1") (pin "4") (pinfunction "4_4") (pintype "passive"))
      (node (ref "X1") (pin "5") (pinfunction "5_5") (pintype "passive"))
      (node (ref "X1") (pin "9") (pinfunction "9_9") (pintype "passive"))
      (node (ref "X3") (pin "3") (pinfunction "3_3") (pintype "passive"))
      (node (ref "X3") (pin "SH1") (pinfunction "PE1_SH1") (pintype "power_in"))
      (node (ref "X3") (pin "SH2") (pinfunction "PE2_SH2") (pintype "power_in"))
      (node (ref "X3") (pin "SH3") (pinfunction "PE3_SH3") (pintype "power_in"))
      (node (ref "X4") (pin "8") (pinfunction "F_8") (pintype "passive"))
      (node (ref "X4") (pin "G1") (pinfunction "G1_G1") (pintype "passive"))
      (node (ref "X5") (pin "8") (pinfunction "F_8") (pintype "passive"))
      (node (ref "X5") (pin "G1") (pinfunction "G1_G1") (pintype "passive"))
      (node (ref "X7") (pin "3") (pinfunction "3_3") (pintype "power_in"))
      (node (ref "X8") (pin "1") (pinfunction "1_1") (pintype "passive"))
    )
    (net (code "91") (name "Net-(C1-Pad2)") (class "Default")
      (node (ref "C1") (pin "2") (pinfunction "2_2") (pintype "passive"))
      (node (ref "R23") (pin "2") (pinfunction "2_2") (pintype "passive"))
      (node (ref "R48") (pin "1") (pinfunction "1_1") (pintype "passive"))
    )
    (net (code "92") (name "Net-(C2-Pad1)") (class "Default")
      (node (ref "C2") (pin "1") (pinfunction "1_1") (pintype "passive"))
      (node (ref "R17") (pin "2") (pinfunction "2_2") (pintype "passive"))
      (node (ref "X8") (pin "2") (pinfunction "2_2") (pintype "passive"))
      (node (ref "X8") (pin "3") (pinfunction "3_3") (pintype "passive"))
      (node (ref "X8") (pin "4") (pinfunction "4_4") (pintype "passive"))
      (node (ref "X8") (pin "5") (pinfunction "5_5") (pintype "passive"))
    )
    (net (code "93") (name "Net-(C3-Pad1)") (class "Default")
      (node (ref "C3") (pin "1") (pinfunction "1_1") (pintype "passive"))
      (node (ref "R48") (pin "2") (pinfunction "2_2") (pintype "passive"))
    )
    (net (code "94") (name "Net-(C4-Pad1)") (class "Default")
      (node (ref "C4") (pin "1") (pinfunction "1_1") (pintype "passive"))
      (node (ref "R49") (pin "2") (pinfunction "2_2") (pintype "passive"))
    )
    (net (code "95") (name "Net-(C5-Pad2)") (class "Default")
      (node (ref "C5") (pin "2") (pinfunction "2_2") (pintype "passive"))
      (node (ref "R34") (pin "2") (pinfunction "2_2") (pintype "passive"))
      (node (ref "R49") (pin "1") (pinfunction "1_1") (pintype "passive"))
    )
    (net (code "96") (name "Net-(IC1-CLK)") (class "Default")
      (node (ref "IC1") (pin "3") (pinfunction "CLK_3") (pintype "bidirectional"))
      (node (ref "U1") (pin "P72") (pinfunction "CCLK_P72") (pintype "bidirectional"))
    )
    (net (code "97") (name "Net-(IC1-TDI)") (class "Default")
      (node (ref "IC1") (pin "4") (pinfunction "TDI_4") (pintype "bidirectional"))
      (node (ref "U1") (pin "P109") (pinfunction "TDO_P109") (pintype "bidirectional"))
    )
    (net (code "98") (name "Net-(IC1-{slash}CE)") (class "Default")
      (node (ref "IC1") (pin "10") (pinfunction "/CE_10") (pintype "bidirectional"))
      (node (ref "U1") (pin "P71") (pinfunction "DONE_P71") (pintype "bidirectional"))
    )
    (net (code "99") (name "Net-(IC1-{slash}CF)") (class "Default")
      (node (ref "IC1") (pin "7") (pinfunction "/CF_7") (pintype "bidirectional"))
      (node (ref "U1") (pin "P143") (pinfunction "PROG_B_P143") (pintype "bidirectional"))
    )
    (net (code "100") (name "Net-(IC3-D+)") (class "Default")
      (node (ref "IC3") (pin "29") (pinfunction "D+_29") (pintype "bidirectional"))
      (node (ref "R54") (pin "2") (pinfunction "2_2") (pintype "passive"))
    )
    (net (code "101") (name "Net-(IC3-D-)") (class "Default")
      (node (ref "IC3") (pin "30") (pinfunction "D-_30") (pintype "bidirectional"))
      (node (ref "R53") (pin "2") (pinfunction "2_2") (pintype "passive"))
    )
    (net (code "102") (name "Net-(IC3-UCAP)") (class "Default")
      (node (ref "C41") (pin "1") (pinfunction "1_1") (pintype "passive"))
      (node (ref "IC3") (pin "27") (pinfunction "UCAP_27") (pintype "bidirectional"))
    )
    (net (code "103") (name "Net-(IC3-UGND)") (class "Default")
      (node (ref "IC3") (pin "28") (pinfunction "UGND_28") (pintype "bidirectional"))
      (node (ref "X6") (pin "4") (pinfunction "4_4") (pintype "passive"))
    )
    (net (code "104") (name "Net-(IC3-XTAL1)") (class "Default")
      (node (ref "C38") (pin "2") (pinfunction "2_2") (pintype "passive"))
      (node (ref "IC3") (pin "1") (pinfunction "XTAL1_1") (pintype "bidirectional"))
      (node (ref "Q1") (pin "2") (pinfunction "2_2") (pintype "passive"))
    )
    (net (code "105") (name "Net-(IC3-XTAL2{slash}PC0)") (class "Default")
      (node (ref "C37") (pin "2") (pinfunction "2_2") (pintype "passive"))
      (node (ref "IC3") (pin "2") (pinfunction "XTAL2/PC0_2") (pintype "bidirectional"))
      (node (ref "Q1") (pin "1") (pinfunction "1_1") (pintype "passive"))
    )
    (net (code "106") (name "Net-(Q5-B)") (class "Default")
      (node (ref "Q5") (pin "1") (pinfunction "B_1") (pintype "passive"))
      (node (ref "R8") (pin "2") (pinfunction "2_2") (pintype "passive"))
    )
    (net (code "107") (name "Net-(Q5-E)") (class "Default")
      (node (ref "Q5") (pin "2") (pinfunction "E_2") (pintype "passive"))
      (node (ref "R13") (pin "2") (pinfunction "2_2") (pintype "passive"))
      (node (ref "R14") (pin "2") (pinfunction "2_2") (pintype "passive"))
    )
    (net (code "108") (name "Net-(Q6-B)") (class "Default")
      (node (ref "Q6") (pin "1") (pinfunction "B_1") (pintype "passive"))
      (node (ref "R10") (pin "2") (pinfunction "2_2") (pintype "passive"))
      (node (ref "R9") (pin "2") (pinfunction "2_2") (pintype "passive"))
    )
    (net (code "109") (name "Net-(Q6-E)") (class "Default")
      (node (ref "Q6") (pin "2") (pinfunction "E_2") (pintype "passive"))
      (node (ref "R15") (pin "2") (pinfunction "2_2") (pintype "passive"))
      (node (ref "R16") (pin "2") (pinfunction "2_2") (pintype "passive"))
      (node (ref "R20") (pin "2") (pinfunction "2_2") (pintype "passive"))
    )
    (net (code "110") (name "Net-(Q7-B)") (class "Default")
      (node (ref "Q7") (pin "1") (pinfunction "B_1") (pintype "passive"))
      (node (ref "R29") (pin "2") (pinfunction "2_2") (pintype "passive"))
      (node (ref "R30") (pin "2") (pinfunction "2_2") (pintype "passive"))
    )
    (net (code "111") (name "Net-(Q7-E)") (class "Default")
      (node (ref "Q7") (pin "2") (pinfunction "E_2") (pintype "passive"))
      (node (ref "R31") (pin "2") (pinfunction "2_2") (pintype "passive"))
      (node (ref "R32") (pin "2") (pinfunction "2_2") (pintype "passive"))
      (node (ref "R33") (pin "2") (pinfunction "2_2") (pintype "passive"))
    )
    (net (code "112") (name "Net-(Q8-B)") (class "Default")
      (node (ref "Q8") (pin "1") (pinfunction "B_1") (pintype "passive"))
      (node (ref "R24") (pin "2") (pinfunction "2_2") (pintype "passive"))
      (node (ref "R25") (pin "2") (pinfunction "2_2") (pintype "passive"))
    )
    (net (code "113") (name "Net-(Q8-E)") (class "Default")
      (node (ref "Q8") (pin "2") (pinfunction "E_2") (pintype "passive"))
      (node (ref "R26") (pin "2") (pinfunction "2_2") (pintype "passive"))
      (node (ref "R27") (pin "2") (pinfunction "2_2") (pintype "passive"))
      (node (ref "R28") (pin "2") (pinfunction "2_2") (pintype "passive"))
    )
    (net (code "114") (name "Net-(R18-Pad2)") (class "Default")
      (node (ref "R18") (pin "2") (pinfunction "2_2") (pintype "passive"))
      (node (ref "R22") (pin "2") (pinfunction "2_2") (pintype "passive"))
    )
    (net (code "115") (name "Net-(R53-Pad1)") (class "Default")
      (node (ref "R53") (pin "1") (pinfunction "1_1") (pintype "passive"))
      (node (ref "X6") (pin "2") (pinfunction "2_2") (pintype "passive"))
    )
    (net (code "116") (name "Net-(R54-Pad1)") (class "Default")
      (node (ref "R54") (pin "1") (pinfunction "1_1") (pintype "passive"))
      (node (ref "X6") (pin "3") (pinfunction "3_3") (pintype "passive"))
    )
    (net (code "117") (name "Net-(T2-B)") (class "Default")
      (node (ref "C2") (pin "2") (pinfunction "2_2") (pintype "passive"))
      (node (ref "R18") (pin "1") (pinfunction "1_1") (pintype "passive"))
      (node (ref "R19") (pin "2") (pinfunction "2_2") (pintype "passive"))
      (node (ref "T2") (pin "1") (pinfunction "B_1") (pintype "passive"))
    )
    (net (code "118") (name "Net-(U$6-A0)") (class "Default")
      (node (ref "U$6") (pin "P20") (pinfunction "A0_P20") (pintype "bidirectional"))
      (node (ref "U1") (pin "P24") (pinfunction "IO_L24N_6VREF_6_P24") (pintype "bidirectional"))
    )
    (net (code "119") (name "Net-(U$6-A1)") (class "Default")
      (node (ref "U$6") (pin "P19") (pinfunction "A1_P19") (pintype "bidirectional"))
      (node (ref "U1") (pin "P23") (pinfunction "IO_L24P_6_P23") (pintype "bidirectional"))
    )
    (net (code "120") (name "Net-(U$6-A2)") (class "Default")
      (node (ref "U$6") (pin "P18") (pinfunction "A2_P18") (pintype "bidirectional"))
      (node (ref "U1") (pin "P21") (pinfunction "IO_L40N_6_P21") (pintype "bidirectional"))
    )
    (net (code "121") (name "Net-(U$6-A3)") (class "Default")
      (node (ref "U$6") (pin "P17") (pinfunction "A3_P17") (pintype "bidirectional"))
      (node (ref "U1") (pin "P20") (pinfunction "IO_L40P_6VREF_6_P20") (pintype "bidirectional"))
    )
    (net (code "122") (name "Net-(U$6-A4)") (class "Default")
      (node (ref "U$6") (pin "P16") (pinfunction "A4_P16") (pintype "bidirectional"))
      (node (ref "U1") (pin "P18") (pinfunction "IO_L40N_7VREF_7_P18") (pintype "bidirectional"))
    )
    (net (code "123") (name "Net-(U$6-A5)") (class "Default")
      (node (ref "U$6") (pin "P15") (pinfunction "A5_P15") (pintype "bidirectional"))
      (node (ref "U1") (pin "P17") (pinfunction "IO_L40P_7_P17") (pintype "bidirectional"))
    )
    (net (code "124") (name "Net-(U$6-A6)") (class "Default")
      (node (ref "U$6") (pin "P14") (pinfunction "A6_P14") (pintype "bidirectional"))
      (node (ref "U1") (pin "P15") (pinfunction "IO_L24N_7_P15") (pintype "bidirectional"))
    )
    (net (code "125") (name "Net-(U$6-A7)") (class "Default")
      (node (ref "U$6") (pin "P13") (pinfunction "A7_P13") (pintype "bidirectional"))
      (node (ref "U1") (pin "P14") (pinfunction "IO_L24P_7_P14") (pintype "bidirectional"))
    )
    (net (code "126") (name "Net-(U$6-A8)") (class "Default")
      (node (ref "U$6") (pin "P3") (pinfunction "A8_P3") (pintype "bidirectional"))
      (node (ref "U1") (pin "P4") (pinfunction "IOVREF_7_P4") (pintype "bidirectional"))
    )
    (net (code "127") (name "Net-(U$6-A9)") (class "Default")
      (node (ref "U$6") (pin "P2") (pinfunction "A9_P2") (pintype "bidirectional"))
      (node (ref "U1") (pin "P2") (pinfunction "IO_L01N_7VRP_7_P2") (pintype "bidirectional"))
    )
    (net (code "128") (name "Net-(U$6-A10)") (class "Default")
      (node (ref "U$6") (pin "P31") (pinfunction "A10_P31") (pintype "bidirectional"))
      (node (ref "U1") (pin "P35") (pinfunction "IO_L01P_6VRN_6_P35") (pintype "bidirectional"))
    )
    (net (code "129") (name "Net-(U$6-A11)") (class "Default")
      (node (ref "U$6") (pin "P1") (pinfunction "A11_P1") (pintype "bidirectional"))
      (node (ref "U1") (pin "P1") (pinfunction "IO_L01P_7VRN_7_P1") (pintype "bidirectional"))
    )
    (net (code "130") (name "Net-(U$6-A12)") (class "Default")
      (node (ref "U$6") (pin "P12") (pinfunction "A12_P12") (pintype "bidirectional"))
      (node (ref "U1") (pin "P13") (pinfunction "IO_L23N_7_P13") (pintype "bidirectional"))
    )
    (net (code "131") (name "Net-(U$6-A13)") (class "Default")
      (node (ref "U$6") (pin "P4") (pinfunction "A13_P4") (pintype "bidirectional"))
      (node (ref "U1") (pin "P5") (pinfunction "IO_L20P_7_P5") (pintype "bidirectional"))
    )
    (net (code "132") (name "Net-(U$6-A14)") (class "Default")
      (node (ref "U$6") (pin "P11") (pinfunction "A14_P11") (pintype "bidirectional"))
      (node (ref "U1") (pin "P12") (pinfunction "IO_L23P_7_P12") (pintype "bidirectional"))
    )
    (net (code "133") (name "Net-(U$6-A15)") (class "Default")
      (node (ref "U$6") (pin "P7") (pinfunction "A15_P7") (pintype "bidirectional"))
      (node (ref "U1") (pin "P8") (pinfunction "IO_L21N_7_P8") (pintype "bidirectional"))
    )
    (net (code "134") (name "Net-(U$6-A16)") (class "Default")
      (node (ref "U$6") (pin "P10") (pinfunction "A16_P10") (pintype "bidirectional"))
      (node (ref "U1") (pin "P11") (pinfunction "IO_L22N_7_P11") (pintype "bidirectional"))
    )
    (net (code "135") (name "Net-(U$6-A17)") (class "Default")
      (node (ref "U$6") (pin "P6") (pinfunction "A17_P6") (pintype "bidirectional"))
      (node (ref "U1") (pin "P7") (pinfunction "IO_L21P_7_P7") (pintype "bidirectional"))
    )
    (net (code "136") (name "Net-(U$6-A18)") (class "Default")
      (node (ref "U$6") (pin "P9") (pinfunction "A18_P9") (pintype "bidirectional"))
      (node (ref "U1") (pin "P10") (pinfunction "IO_L22P_7_P10") (pintype "bidirectional"))
    )
    (net (code "137") (name "Net-(U$6-DQ0)") (class "Default")
      (node (ref "U$6") (pin "P21") (pinfunction "DQ0_P21") (pintype "bidirectional"))
      (node (ref "U1") (pin "P25") (pinfunction "IO_L23P_6_P25") (pintype "bidirectional"))
    )
    (net (code "138") (name "Net-(U$6-DQ1)") (class "Default")
      (node (ref "U$6") (pin "P22") (pinfunction "DQ1_P22") (pintype "bidirectional"))
      (node (ref "U1") (pin "P26") (pinfunction "IO_L23N_6_P26") (pintype "bidirectional"))
    )
    (net (code "139") (name "Net-(U$6-DQ2)") (class "Default")
      (node (ref "U$6") (pin "P23") (pinfunction "DQ2_P23") (pintype "bidirectional"))
      (node (ref "U1") (pin "P27") (pinfunction "IO_L22P_6_P27") (pintype "bidirectional"))
    )
    (net (code "140") (name "Net-(U$6-DQ3)") (class "Default")
      (node (ref "U$6") (pin "P25") (pinfunction "DQ3_P25") (pintype "bidirectional"))
      (node (ref "U1") (pin "P28") (pinfunction "IO_L22N_6_P28") (pintype "bidirectional"))
    )
    (net (code "141") (name "Net-(U$6-DQ4)") (class "Default")
      (node (ref "U$6") (pin "P26") (pinfunction "DQ4_P26") (pintype "bidirectional"))
      (node (ref "U1") (pin "P30") (pinfunction "IO_L21P_6_P30") (pintype "bidirectional"))
    )
    (net (code "142") (name "Net-(U$6-DQ5)") (class "Default")
      (node (ref "U$6") (pin "P27") (pinfunction "DQ5_P27") (pintype "bidirectional"))
      (node (ref "U1") (pin "P31") (pinfunction "IO_L21N_6_P31") (pintype "bidirectional"))
    )
    (net (code "143") (name "Net-(U$6-DQ6)") (class "Default")
      (node (ref "U$6") (pin "P28") (pinfunction "DQ6_P28") (pintype "bidirectional"))
      (node (ref "U1") (pin "P32") (pinfunction "IO_L20P_6_P32") (pintype "bidirectional"))
    )
    (net (code "144") (name "Net-(U$6-DQ7)") (class "Default")
      (node (ref "U$6") (pin "P29") (pinfunction "DQ7_P29") (pintype "bidirectional"))
      (node (ref "U1") (pin "P33") (pinfunction "IO_L20N_6_P33") (pintype "bidirectional"))
    )
    (net (code "145") (name "Net-(U$6-OE)") (class "Default")
      (node (ref "U$6") (pin "P32") (pinfunction "OE_P32") (pintype "bidirectional"))
      (node (ref "U1") (pin "P36") (pinfunction "IO_L01N_6VRP_6_P36") (pintype "bidirectional"))
    )
    (net (code "146") (name "Net-(U$6-WE)") (class "Default")
      (node (ref "U$6") (pin "P5") (pinfunction "WE_P5") (pintype "bidirectional"))
      (node (ref "U1") (pin "P6") (pinfunction "IO_L20N_7_P6") (pintype "bidirectional"))
    )
    (net (code "147") (name "Net-(U1A-IO_L27N_0)") (class "Default")
      (node (ref "SV3") (pin "3") (pinfunction "3_3") (pintype "passive"))
      (node (ref "U1") (pin "P137") (pinfunction "IO_L27N_0_P137") (pintype "bidirectional"))
    )
    (net (code "148") (name "Net-(U1A-IO_L27P_0)") (class "Default")
      (node (ref "SV3") (pin "4") (pinfunction "4_4") (pintype "passive"))
      (node (ref "U1") (pin "P135") (pinfunction "IO_L27P_0_P135") (pintype "bidirectional"))
    )
    (net (code "149") (name "Net-(U1A-IO_L30N_0)") (class "Default")
      (node (ref "SV3") (pin "5") (pinfunction "5_5") (pintype "passive"))
      (node (ref "U1") (pin "P132") (pinfunction "IO_L30N_0_P132") (pintype "bidirectional"))
    )
    (net (code "150") (name "Net-(U1A-IO_L30P_0)") (class "Default")
      (node (ref "SV3") (pin "6") (pinfunction "6_6") (pintype "passive"))
      (node (ref "U1") (pin "P131") (pinfunction "IO_L30P_0_P131") (pintype "bidirectional"))
    )
    (net (code "151") (name "Net-(U1A-IO_L31N_0)") (class "Default")
      (node (ref "SV3") (pin "7") (pinfunction "7_7") (pintype "passive"))
      (node (ref "U1") (pin "P130") (pinfunction "IO_L31N_0_P130") (pintype "bidirectional"))
    )
    (net (code "152") (name "Net-(U1A-IO_L31P_0VREF_0)") (class "Default")
      (node (ref "SV3") (pin "8") (pinfunction "8_8") (pintype "passive"))
      (node (ref "U1") (pin "P129") (pinfunction "IO_L31P_0VREF_0_P129") (pintype "bidirectional"))
    )
    (net (code "153") (name "Net-(U1A-IO_L32N_0GCLK7)") (class "Default")
      (node (ref "SV3") (pin "9") (pinfunction "9_9") (pintype "passive"))
      (node (ref "U1") (pin "P128") (pinfunction "IO_L32N_0GCLK7_P128") (pintype "bidirectional"))
    )
    (net (code "154") (name "Net-(U1C-IO_L32N_1GCLK5)") (class "Default")
      (node (ref "SV3") (pin "10") (pinfunction "10_10") (pintype "passive"))
      (node (ref "U1") (pin "P125") (pinfunction "IO_L32N_1GCLK5_P125") (pintype "bidirectional"))
    )
    (net (code "155") (name "Net-(U1G-IO_L32P_4GCLK0)") (class "Default")
      (node (ref "SV1") (pin "10") (pinfunction "10_10") (pintype "passive"))
      (node (ref "U1") (pin "P55") (pinfunction "IO_L32P_4GCLK0_P55") (pintype "bidirectional"))
    )
    (net (code "156") (name "Net-(U1N-TCK)") (class "Default")
      (node (ref "R2") (pin "1") (pinfunction "1_1") (pintype "passive"))
      (node (ref "U1") (pin "P110") (pinfunction "TCK_P110") (pintype "bidirectional"))
    )
    (net (code "157") (name "Net-(U1N-TDI)") (class "Default")
      (node (ref "R1") (pin "1") (pinfunction "1_1") (pintype "passive"))
      (node (ref "U1") (pin "P144") (pinfunction "TDI_P144") (pintype "bidirectional"))
    )
    (net (code "158") (name "Net-(U1N-TMS)") (class "Default")
      (node (ref "R3") (pin "1") (pinfunction "1_1") (pintype "passive"))
      (node (ref "U1") (pin "P111") (pinfunction "TMS_P111") (pintype "bidirectional"))
    )
    (net (code "159") (name "unconnected-(IC1-NC.1-Pad2)") (class "Default")
      (node (ref "IC1") (pin "2") (pinfunction "NC.1_2") (pintype "bidirectional"))
    )
    (net (code "160") (name "unconnected-(IC1-NC.2-Pad9)") (class "Default")
      (node (ref "IC1") (pin "9") (pinfunction "NC.2_9") (pintype "bidirectional"))
    )
    (net (code "161") (name "unconnected-(IC1-NC.3-Pad12)") (class "Default")
      (node (ref "IC1") (pin "12") (pinfunction "NC.3_12") (pintype "bidirectional"))
    )
    (net (code "162") (name "unconnected-(IC1-NC.4-Pad14)") (class "Default")
      (node (ref "IC1") (pin "14") (pinfunction "NC.4_14") (pintype "bidirectional"))
    )
    (net (code "163") (name "unconnected-(IC1-NC.5-Pad15)") (class "Default")
      (node (ref "IC1") (pin "15") (pinfunction "NC.5_15") (pintype "bidirectional"))
    )
    (net (code "164") (name "unconnected-(IC1-NC.6-Pad16)") (class "Default")
      (node (ref "IC1") (pin "16") (pinfunction "NC.6_16") (pintype "bidirectional"))
    )
    (net (code "165") (name "unconnected-(IC1-{slash}CEO-Pad13)") (class "Default")
      (node (ref "IC1") (pin "13") (pinfunction "/CEO_13") (pintype "bidirectional"))
    )
    (net (code "166") (name "unconnected-(JP1-Pad3)") (class "Default")
      (node (ref "JP1") (pin "3") (pinfunction "3_3") (pintype "passive"))
    )
    (net (code "167") (name "unconnected-(JP1-Pad4)") (class "Default")
      (node (ref "JP1") (pin "4") (pinfunction "4_4") (pintype "passive"))
    )
    (net (code "168") (name "unconnected-(JP1-Pad5)") (class "Default")
      (node (ref "JP1") (pin "5") (pinfunction "5_5") (pintype "passive"))
    )
    (net (code "169") (name "unconnected-(JP1-Pad6)") (class "Default")
      (node (ref "JP1") (pin "6") (pinfunction "6_6") (pintype "passive"))
    )
    (net (code "170") (name "unconnected-(JP1-Pad7)") (class "Default")
      (node (ref "JP1") (pin "7") (pinfunction "7_7") (pintype "passive"))
    )
    (net (code "171") (name "unconnected-(JP1-Pad8)") (class "Default")
      (node (ref "JP1") (pin "8") (pinfunction "8_8") (pintype "passive"))
    )
    (net (code "172") (name "unconnected-(JP1-Pad9)") (class "Default")
      (node (ref "JP1") (pin "9") (pinfunction "9_9") (pintype "passive"))
    )
    (net (code "173") (name "unconnected-(JP1-Pad10)") (class "Default")
      (node (ref "JP1") (pin "10") (pinfunction "10_10") (pintype "passive"))
    )
    (net (code "174") (name "unconnected-(JP1-Pad11)") (class "Default")
      (node (ref "JP1") (pin "11") (pinfunction "11_11") (pintype "passive"))
    )
    (net (code "175") (name "unconnected-(JP1-Pad12)") (class "Default")
      (node (ref "JP1") (pin "12") (pinfunction "12_12") (pintype "passive"))
    )
    (net (code "176") (name "unconnected-(JP1-Pad13)") (class "Default")
      (node (ref "JP1") (pin "13") (pinfunction "13_13") (pintype "passive"))
    )
    (net (code "177") (name "unconnected-(JP1-Pad14)") (class "Default")
      (node (ref "JP1") (pin "14") (pinfunction "14_14") (pintype "passive"))
    )
    (net (code "178") (name "unconnected-(JP1-Pad15)") (class "Default")
      (node (ref "JP1") (pin "15") (pinfunction "15_15") (pintype "passive"))
    )
    (net (code "179") (name "unconnected-(JP1-Pad16)") (class "Default")
      (node (ref "JP1") (pin "16") (pinfunction "16_16") (pintype "passive"))
    )
    (net (code "180") (name "unconnected-(JP1-Pad17)") (class "Default")
      (node (ref "JP1") (pin "17") (pinfunction "17_17") (pintype "passive"))
    )
    (net (code "181") (name "unconnected-(JP1-Pad18)") (class "Default")
      (node (ref "JP1") (pin "18") (pinfunction "18_18") (pintype "passive"))
    )
    (net (code "182") (name "unconnected-(JP1-Pad19)") (class "Default")
      (node (ref "JP1") (pin "19") (pinfunction "19_19") (pintype "passive"))
    )
    (net (code "183") (name "unconnected-(JP1-Pad20)") (class "Default")
      (node (ref "JP1") (pin "20") (pinfunction "20_20") (pintype "passive"))
    )
    (net (code "184") (name "unconnected-(REG1.2-VOUT2-Pad2)") (class "Default")
      (node (ref "REG1.2") (pin "2") (pinfunction "VOUT2_2") (pintype "bidirectional"))
    )
    (net (code "185") (name "unconnected-(REG2.5-VOUT2-Pad2)") (class "Default")
      (node (ref "REG2.5") (pin "2") (pinfunction "VOUT2_2") (pintype "bidirectional"))
    )
    (net (code "186") (name "unconnected-(SJ1-Pad1)") (class "Default")
      (node (ref "SJ1") (pin "1") (pinfunction "1_1") (pintype "passive"))
    )
    (net (code "187") (name "unconnected-(SJ1-Pad2)") (class "Default")
      (node (ref "SJ1") (pin "2") (pinfunction "2_2") (pintype "passive"))
    )
    (net (code "188") (name "unconnected-(SJ2-Pad1)") (class "Default")
      (node (ref "SJ2") (pin "1") (pinfunction "1_1") (pintype "passive"))
    )
    (net (code "189") (name "unconnected-(SJ2-Pad2)") (class "Default")
      (node (ref "SJ2") (pin "2") (pinfunction "2_2") (pintype "passive"))
    )
    (net (code "190") (name "unconnected-(T4-B-Pad1)") (class "Default")
      (node (ref "T4") (pin "1") (pinfunction "B_1") (pintype "passive"))
    )
    (net (code "191") (name "unconnected-(T4-C-Pad3)") (class "Default")
      (node (ref "T4") (pin "3") (pinfunction "C_3") (pintype "passive"))
    )
    (net (code "192") (name "unconnected-(T4-E-Pad2)") (class "Default")
      (node (ref "T4") (pin "2") (pinfunction "E_2") (pintype "passive"))
    )
    (net (code "193") (name "unconnected-(U$2-TRI-PadENA)") (class "Default")
      (node (ref "U$2") (pin "ENA") (pinfunction "TRI_ENA") (pintype "input"))
    )
    (net (code "194") (name "unconnected-(U$3-CARD_DETECT-PadCD)") (class "Default")
      (node (ref "U$3") (pin "CD") (pinfunction "CARD_DETECT_CD") (pintype "passive"))
    )
    (net (code "195") (name "unconnected-(U$3-DAT1-Pad8)") (class "Default")
      (node (ref "U$3") (pin "8") (pinfunction "DAT1_8") (pintype "bidirectional"))
    )
    (net (code "196") (name "unconnected-(U$3-DAT2-Pad9)") (class "Default")
      (node (ref "U$3") (pin "9") (pinfunction "DAT2_9") (pintype "bidirectional"))
    )
    (net (code "197") (name "unconnected-(U$3-WRITE_PROTECT-PadWP)") (class "Default")
      (node (ref "U$3") (pin "WP") (pinfunction "WRITE_PROTECT_WP") (pintype "passive"))
    )
    (net (code "198") (name "unconnected-(U$4-VOUT2-Pad2)") (class "Default")
      (node (ref "U$4") (pin "2") (pinfunction "VOUT2_2") (pintype "bidirectional"))
    )
    (net (code "199") (name "unconnected-(U1F-IO-PadP76)") (class "Default")
      (node (ref "U1") (pin "P76") (pinfunction "IO_P76") (pintype "bidirectional"))
    )
    (net (code "200") (name "unconnected-(U1F-IO_L01N_3VRP_3-PadP74)") (class "Default")
      (node (ref "U1") (pin "P74") (pinfunction "IO_L01N_3VRP_3_P74") (pintype "bidirectional"))
    )
    (net (code "201") (name "unconnected-(U1F-IO_L01P_3VRN_3-PadP73)") (class "Default")
      (node (ref "U1") (pin "P73") (pinfunction "IO_L01P_3VRN_3_P73") (pintype "bidirectional"))
    )
    (net (code "202") (name "unconnected-(U1F-IO_L20N_3-PadP78)") (class "Default")
      (node (ref "U1") (pin "P78") (pinfunction "IO_L20N_3_P78") (pintype "bidirectional"))
    )
    (net (code "203") (name "unconnected-(U1F-IO_L20P_3-PadP77)") (class "Default")
      (node (ref "U1") (pin "P77") (pinfunction "IO_L20P_3_P77") (pintype "bidirectional"))
    )
    (net (code "204") (name "unconnected-(U1F-IO_L21N_3-PadP80)") (class "Default")
      (node (ref "U1") (pin "P80") (pinfunction "IO_L21N_3_P80") (pintype "bidirectional"))
    )
    (net (code "205") (name "unconnected-(U1F-IO_L21P_3-PadP79)") (class "Default")
      (node (ref "U1") (pin "P79") (pinfunction "IO_L21P_3_P79") (pintype "bidirectional"))
    )
    (net (code "206") (name "unconnected-(U1F-IO_L22N_3-PadP83)") (class "Default")
      (node (ref "U1") (pin "P83") (pinfunction "IO_L22N_3_P83") (pintype "bidirectional"))
    )
    (net (code "207") (name "unconnected-(U1F-IO_L22P_3-PadP82)") (class "Default")
      (node (ref "U1") (pin "P82") (pinfunction "IO_L22P_3_P82") (pintype "bidirectional"))
    )
    (net (code "208") (name "unconnected-(U1F-IO_L23N_3-PadP85)") (class "Default")
      (node (ref "U1") (pin "P85") (pinfunction "IO_L23N_3_P85") (pintype "bidirectional"))
    )
    (net (code "209") (name "unconnected-(U1F-IO_L23P_3VREF_3-PadP84)") (class "Default")
      (node (ref "U1") (pin "P84") (pinfunction "IO_L23P_3VREF_3_P84") (pintype "bidirectional"))
    )
    (net (code "210") (name "unconnected-(U1F-IO_L24N_3-PadP87)") (class "Default")
      (node (ref "U1") (pin "P87") (pinfunction "IO_L24N_3_P87") (pintype "bidirectional"))
    )
    (net (code "211") (name "unconnected-(U1F-IO_L24P_3-PadP86)") (class "Default")
      (node (ref "U1") (pin "P86") (pinfunction "IO_L24P_3_P86") (pintype "bidirectional"))
    )
    (net (code "212") (name "unconnected-(U1F-IO_L40N_3VREF_3-PadP90)") (class "Default")
      (node (ref "U1") (pin "P90") (pinfunction "IO_L40N_3VREF_3_P90") (pintype "bidirectional"))
    )
    (net (code "213") (name "unconnected-(U1F-IO_L40P_3-PadP89)") (class "Default")
      (node (ref "U1") (pin "P89") (pinfunction "IO_L40P_3_P89") (pintype "bidirectional"))
    )
    (net (code "214") (name "unconnected-(U1G-IO_L31P_4DOUTBUSY-PadP57)") (class "Default")
      (node (ref "U1") (pin "P57") (pinfunction "IO_L31P_4DOUTBUSY_P57") (pintype "bidirectional"))
    )
    (net (code "215") (name "unconnected-(U1N-HSWAP_EN-PadP142)") (class "Default")
      (node (ref "U1") (pin "P142") (pinfunction "HSWAP_EN_P142") (pintype "bidirectional"))
    )
    (net (code "216") (name "unconnected-(X1-Pad10)") (class "Default")
      (node (ref "X1") (pin "10") (pinfunction "10_10") (pintype "passive"))
    )
    (net (code "217") (name "unconnected-(X1-Pad12)") (class "Default")
      (node (ref "X1") (pin "12") (pinfunction "12_12") (pintype "passive"))
    )
    (net (code "218") (name "unconnected-(X3-Pad2)") (class "Default")
      (node (ref "X3") (pin "2") (pinfunction "2_2") (pintype "passive"))
    )
    (net (code "219") (name "unconnected-(X3-Pad8)") (class "Default")
      (node (ref "X3") (pin "8") (pinfunction "8_8") (pintype "passive"))
    )
    (net (code "220") (name "unconnected-(X4-PadG2)") (class "Default")
      (node (ref "X4") (pin "G2") (pinfunction "G2_G2") (pintype "passive"))
    )
    (net (code "221") (name "unconnected-(X5-PadG2)") (class "Default")
      (node (ref "X5") (pin "G2") (pinfunction "G2_G2") (pintype "passive"))
    )
    (net (code "222") (name "unconnected-(X6-Pad1)") (class "Default")
      (node (ref "X6") (pin "1") (pinfunction "1_1") (pintype "passive"))
    )
  )
)
